# InstrumentHubs.net
KiCad netlist of a schematic drawn in EAGLE
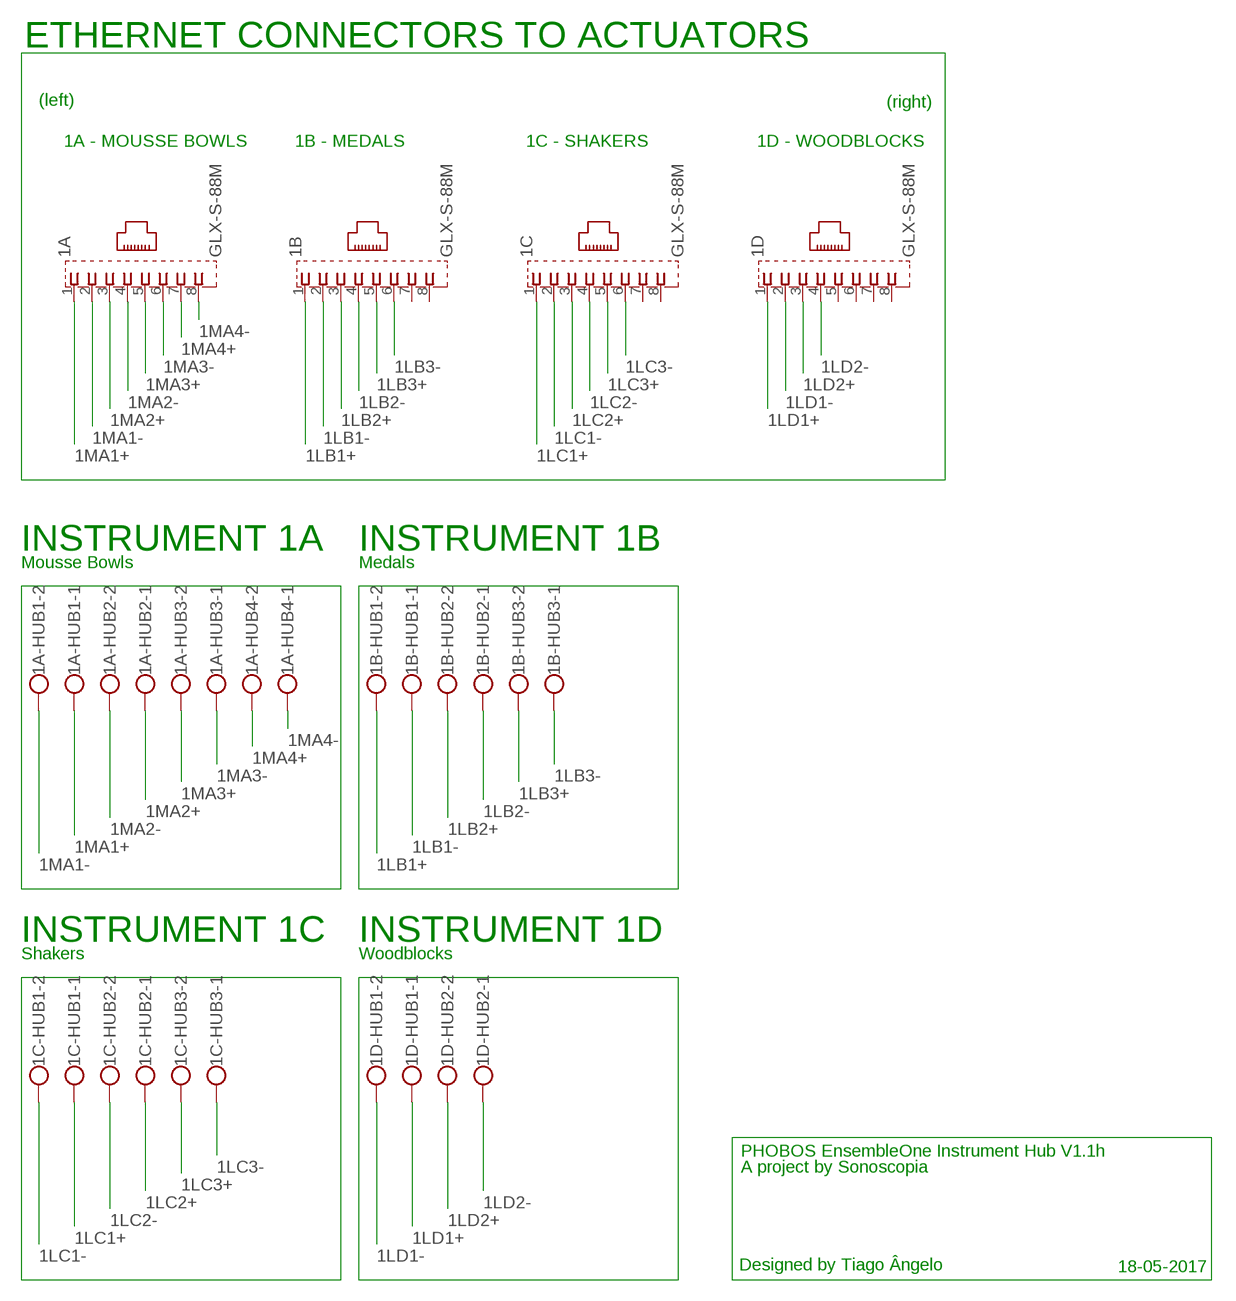
[diagram p0: schematic, sheet 1]
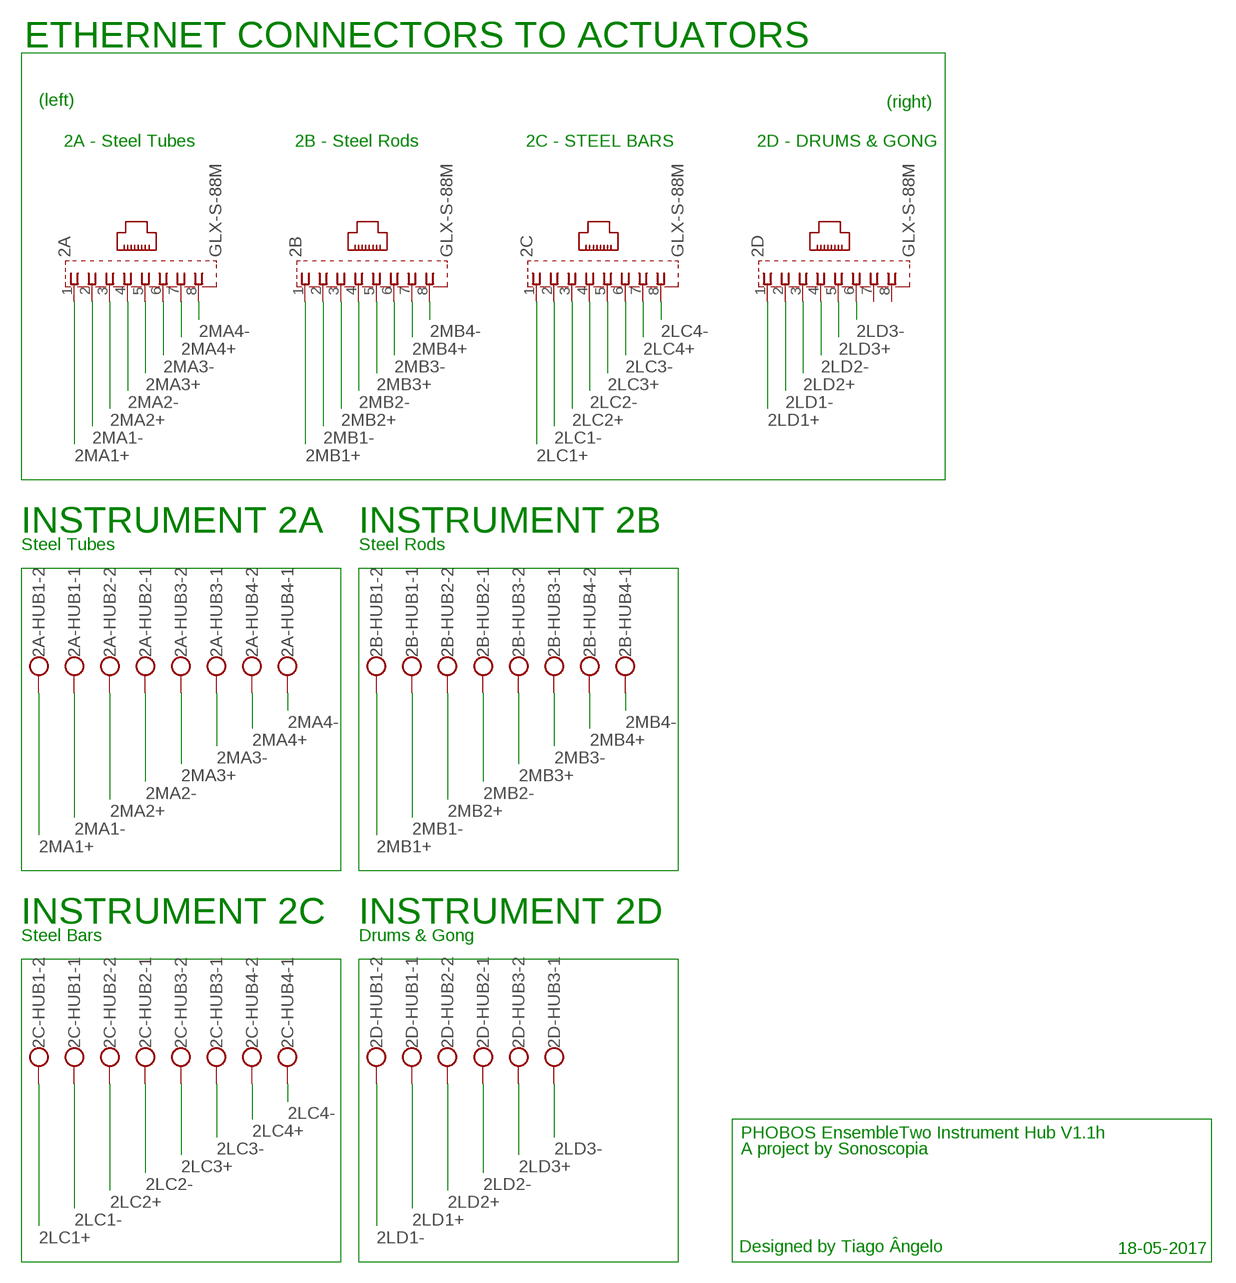
[diagram p1: schematic, sheet 2]
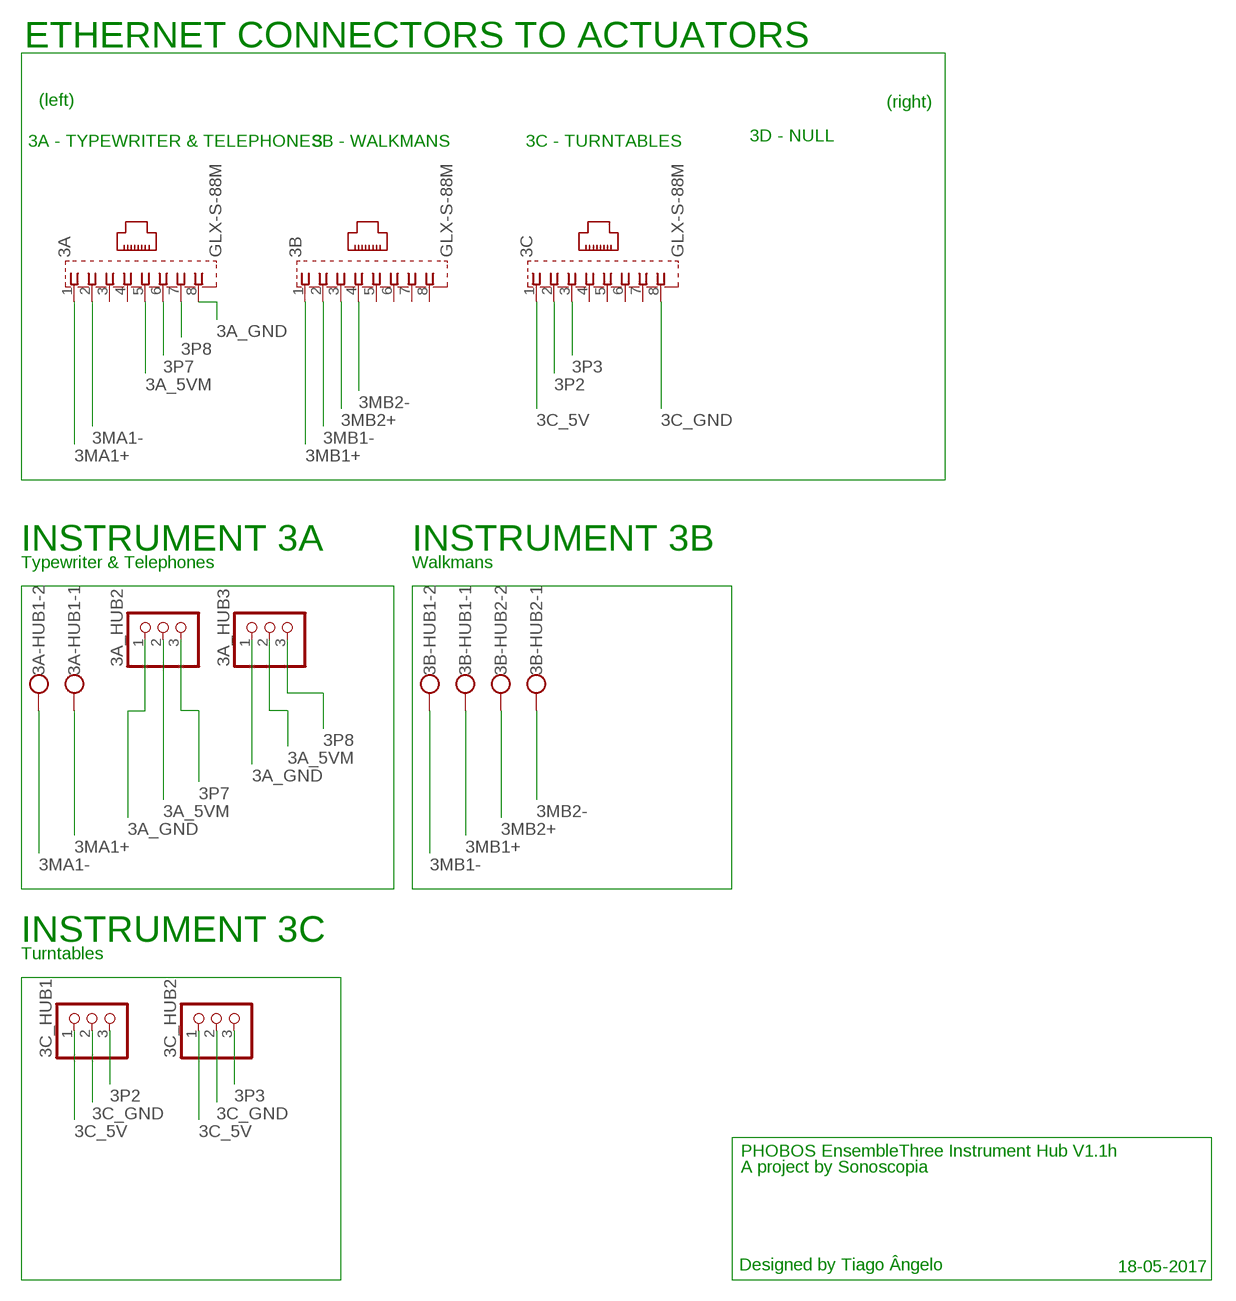
[diagram p2: schematic, sheet 3]
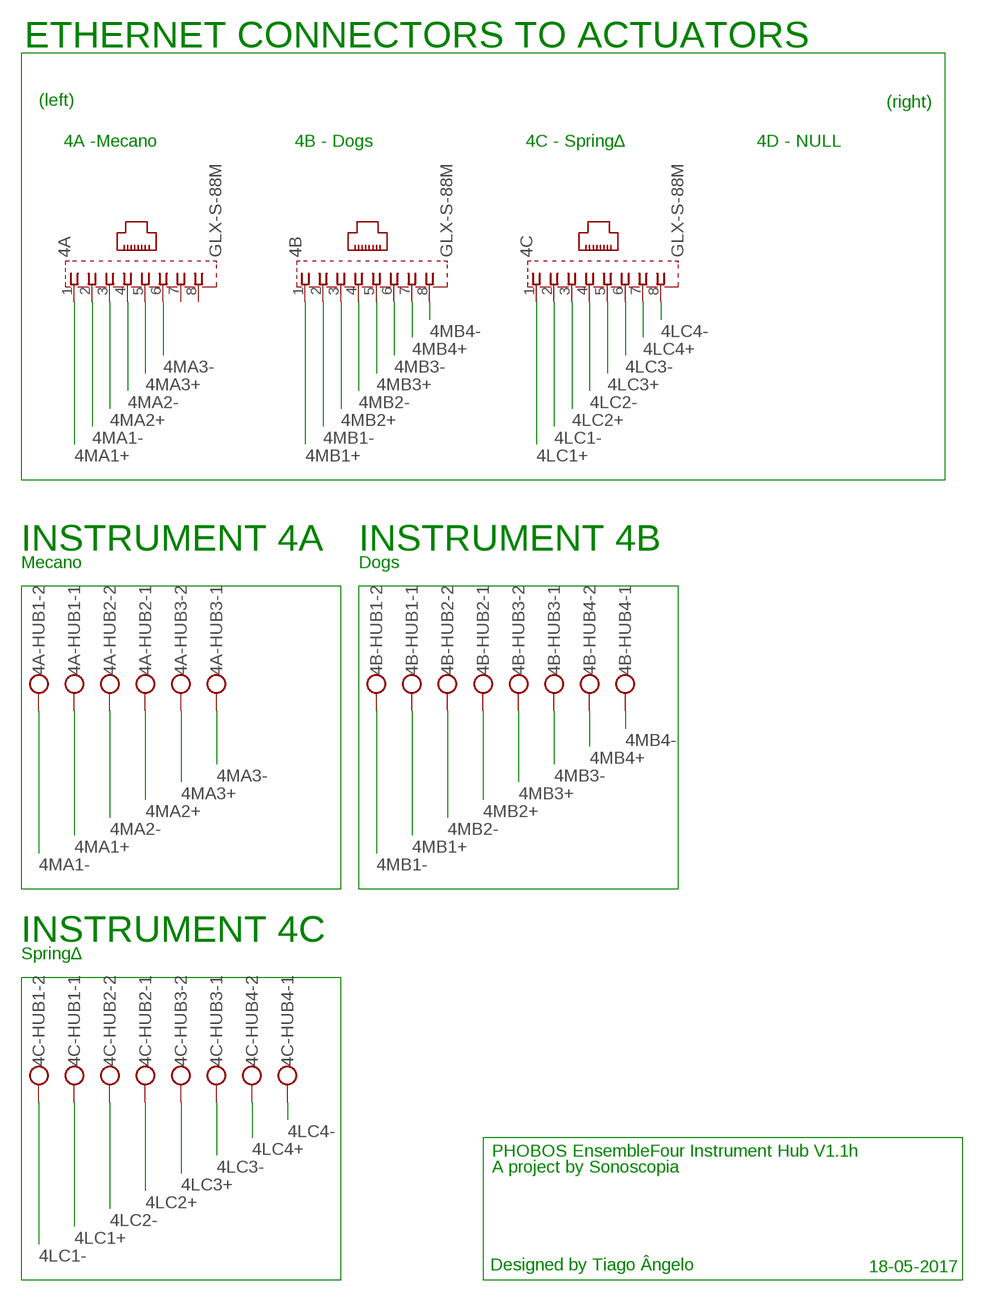
[diagram p3: schematic, sheet 4]
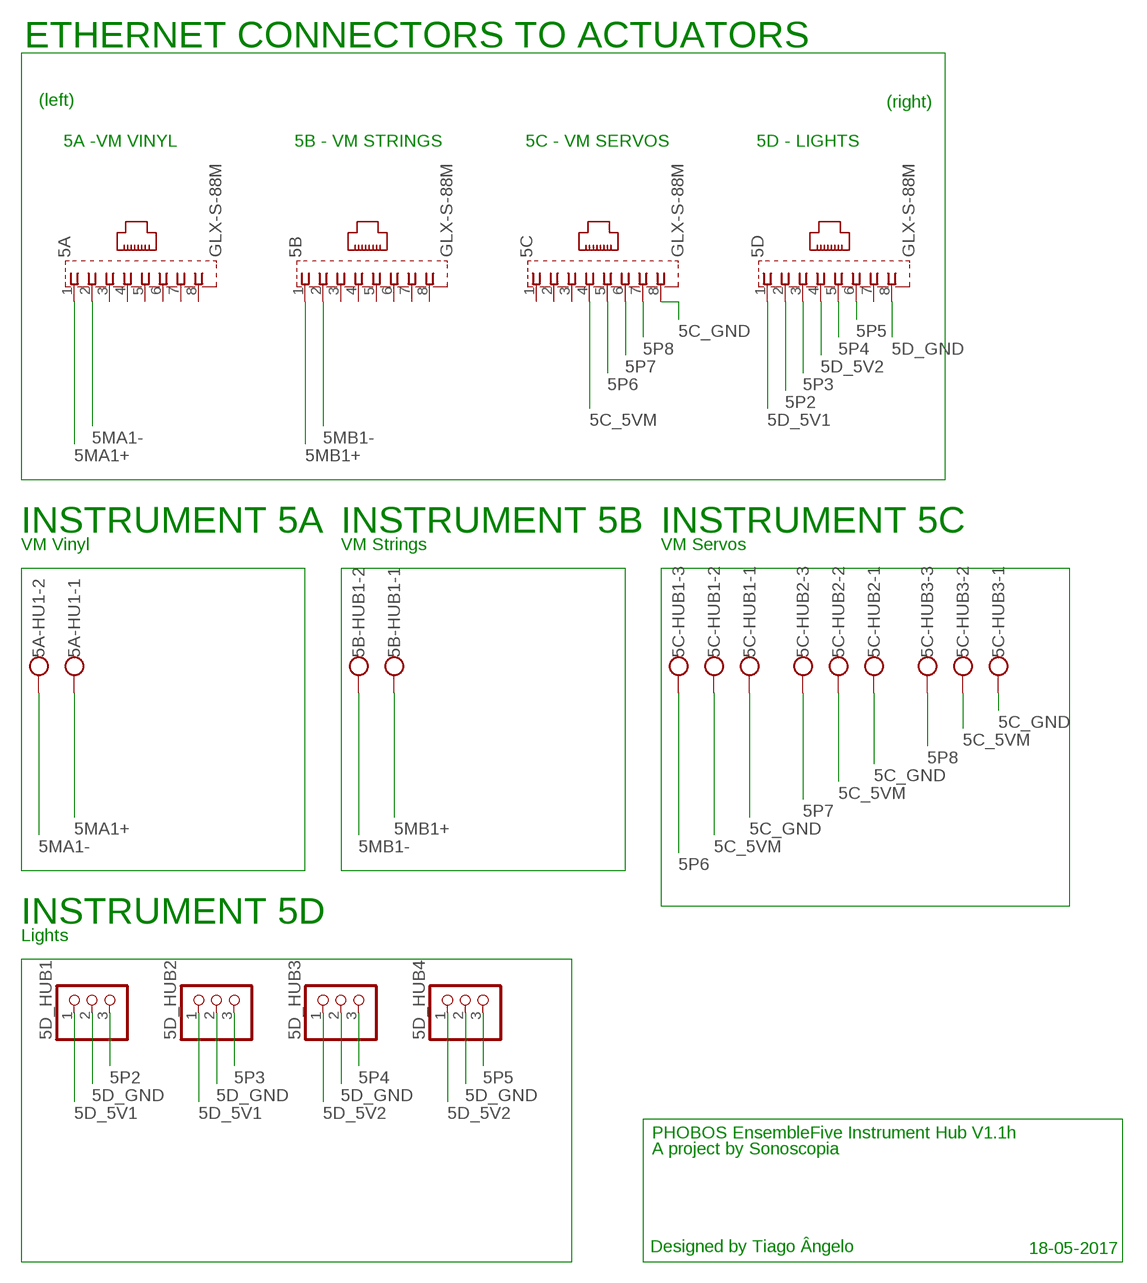
[diagram p4: schematic, sheet 5]
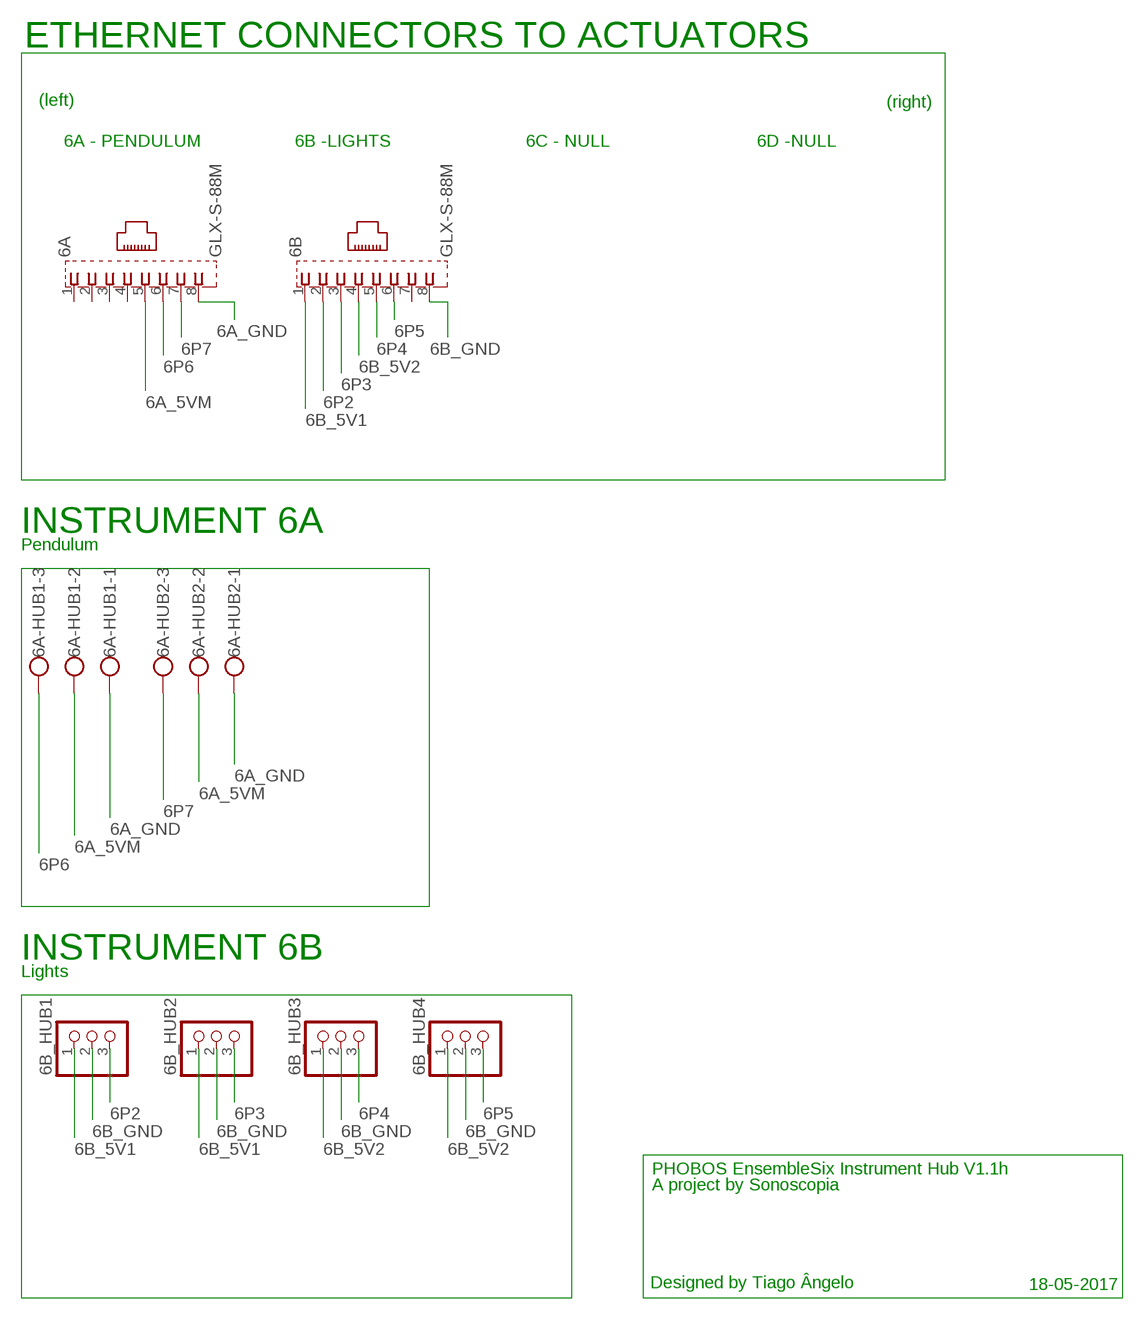
[diagram p5: schematic, sheet 6]
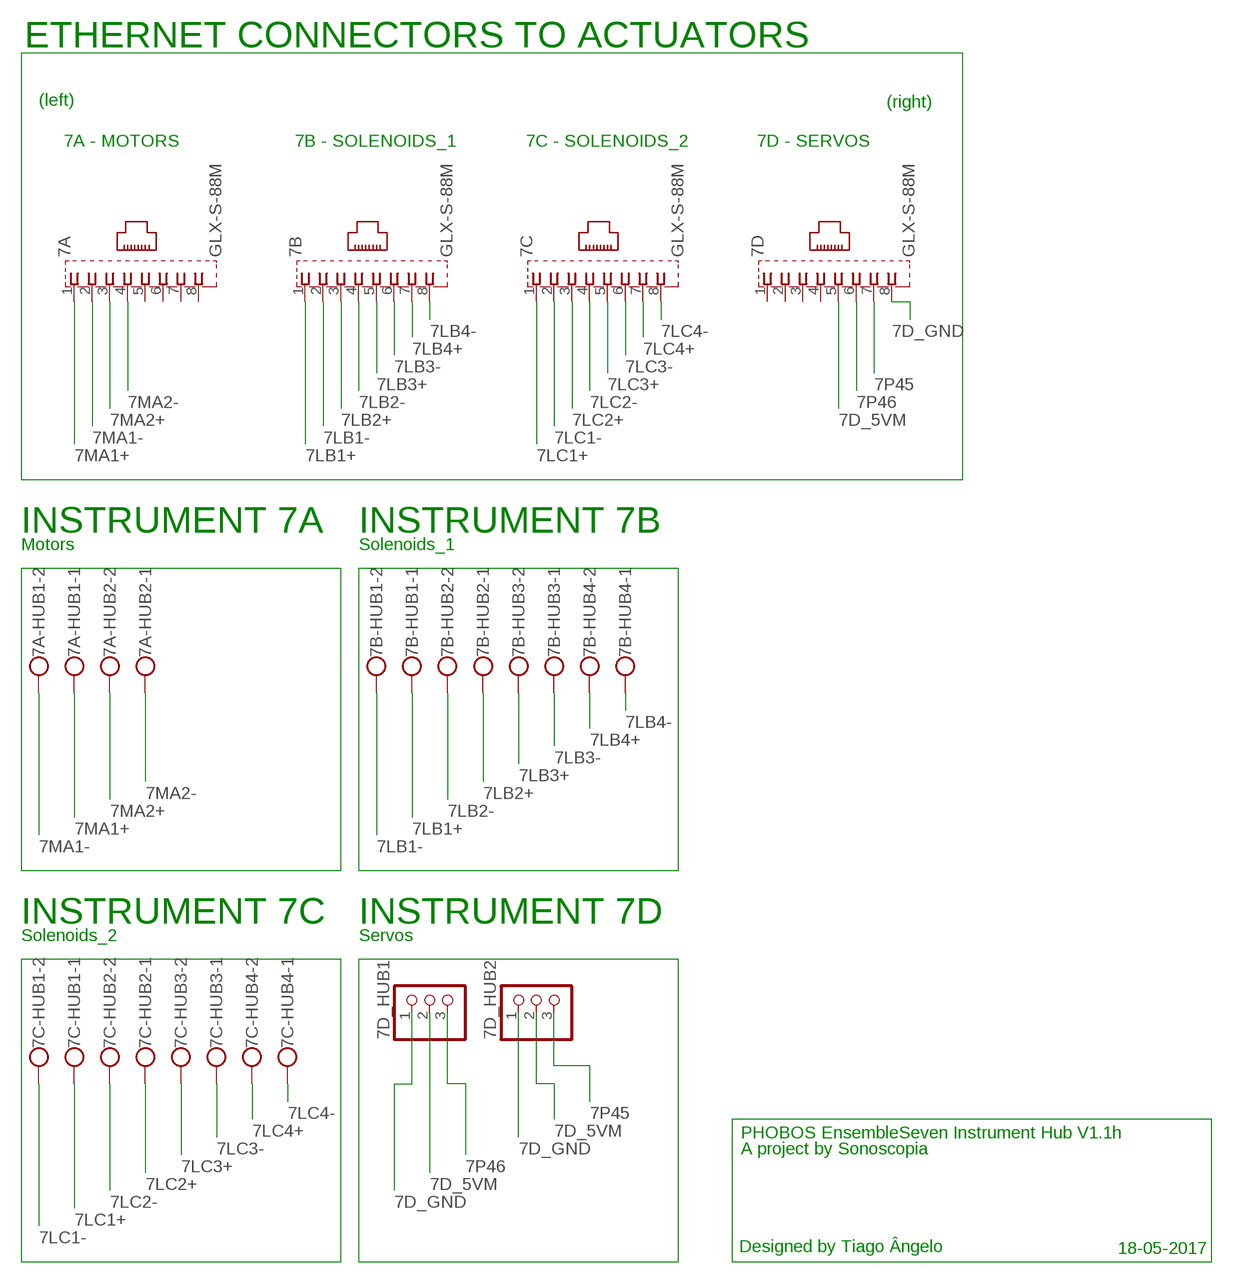
[diagram p6: schematic, sheet 7]
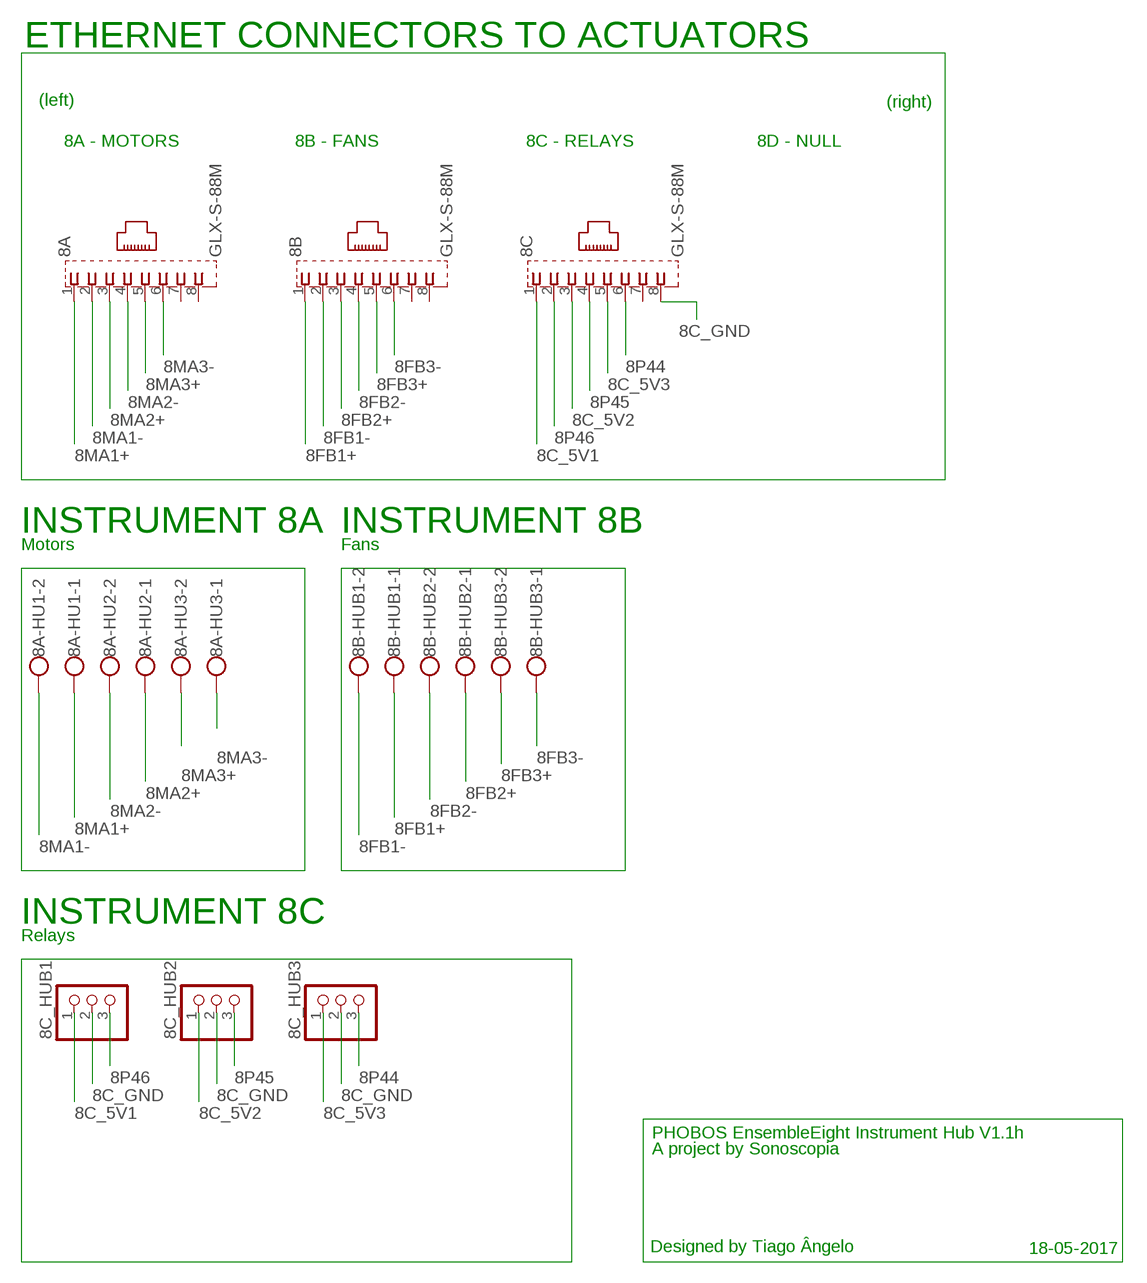
[diagram p7: schematic, sheet 8]
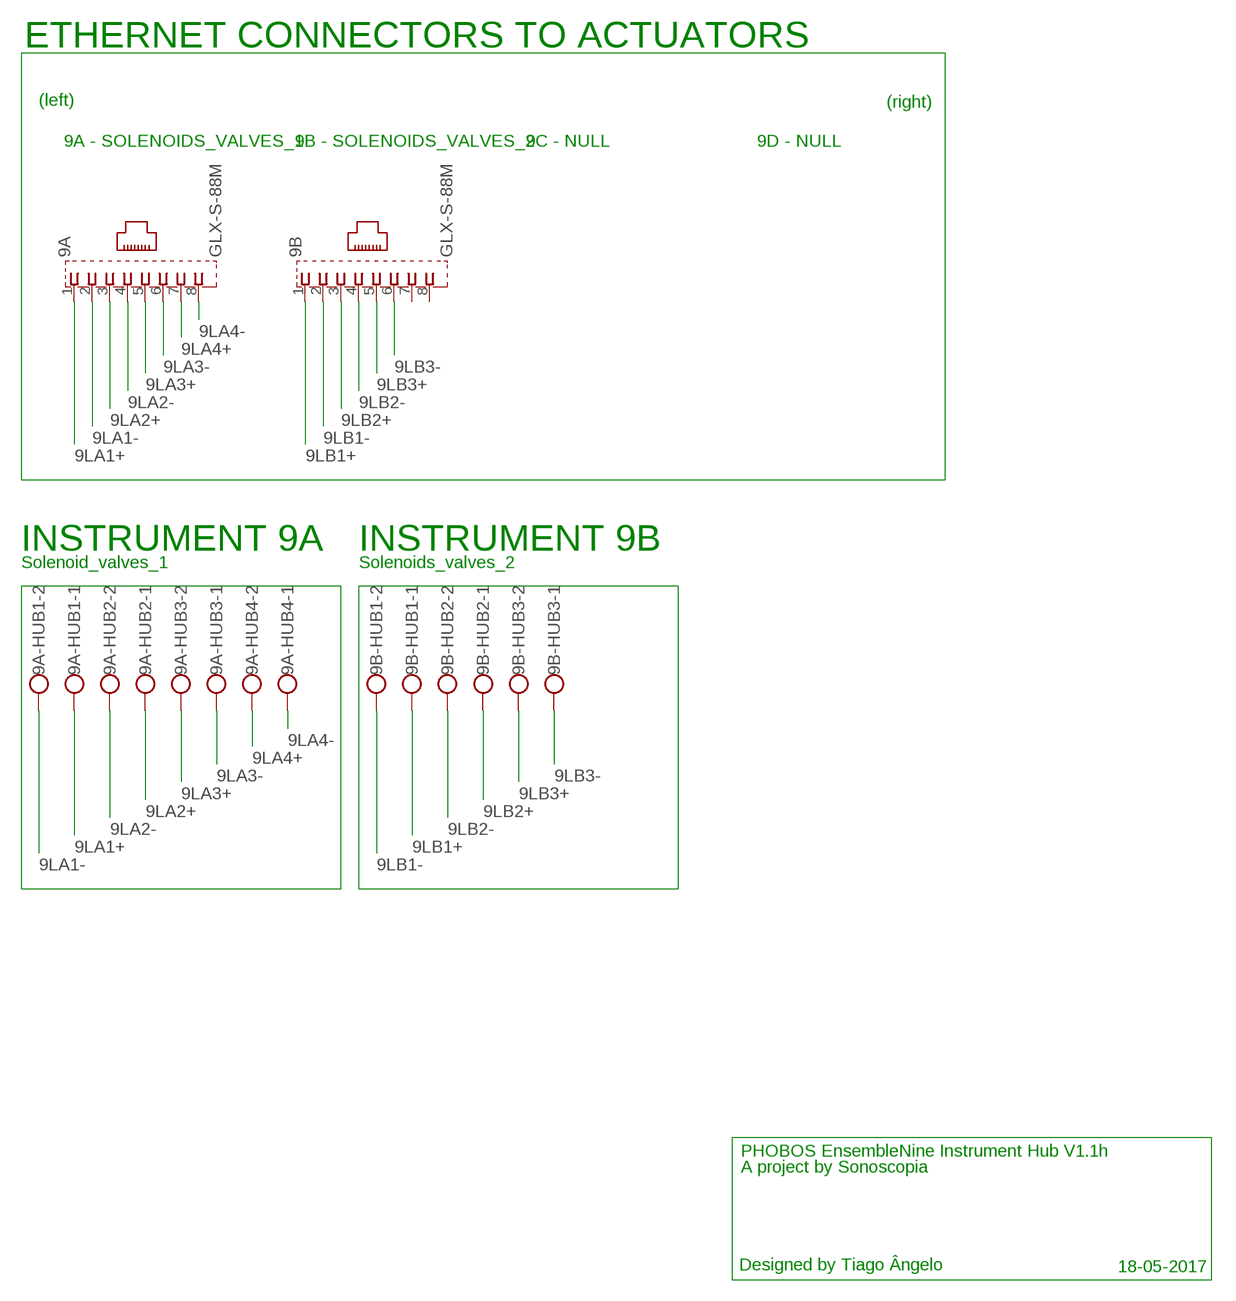
[diagram p8: schematic, sheet 9]

(export (version "E")
  (design (tool "Eeschema 10.0.6"))
  (components
    (comp (ref "7A")
      (value "GLX-S-88M")
      (footprint "eagle-import:GLX-S-88M")
      (libsource (lib "eagle-import") (part "GLX-S-88M"))
    )
    (comp (ref "7A-HUB1")
      (value "W237-102")
      (footprint "eagle-import:W237-102")
      (fields (field (name "MPN") "237-102"))
      (libsource (lib "eagle-import") (part "W237-102"))
    )
    (comp (ref "7A-HUB2")
      (value "W237-102")
      (footprint "eagle-import:W237-102")
      (fields (field (name "MPN") "237-102"))
      (libsource (lib "eagle-import") (part "W237-102"))
    )
    (comp (ref "7B")
      (value "GLX-S-88M")
      (footprint "eagle-import:GLX-S-88M")
      (libsource (lib "eagle-import") (part "GLX-S-88M"))
    )
    (comp (ref "7B-HUB1")
      (value "W237-102")
      (footprint "eagle-import:W237-102")
      (fields (field (name "MPN") "237-102"))
      (libsource (lib "eagle-import") (part "W237-102"))
    )
    (comp (ref "7B-HUB2")
      (value "W237-102")
      (footprint "eagle-import:W237-102")
      (fields (field (name "MPN") "237-102"))
      (libsource (lib "eagle-import") (part "W237-102"))
    )
    (comp (ref "7B-HUB3")
      (value "W237-102")
      (footprint "eagle-import:W237-102")
      (fields (field (name "MPN") "237-102"))
      (libsource (lib "eagle-import") (part "W237-102"))
    )
    (comp (ref "7B-HUB4")
      (value "W237-102")
      (footprint "eagle-import:W237-102")
      (fields (field (name "MPN") "237-102"))
      (libsource (lib "eagle-import") (part "W237-102"))
    )
    (comp (ref "7C")
      (value "GLX-S-88M")
      (footprint "eagle-import:GLX-S-88M")
      (libsource (lib "eagle-import") (part "GLX-S-88M"))
    )
    (comp (ref "7C-HUB1")
      (value "W237-102")
      (footprint "eagle-import:W237-102")
      (fields (field (name "MPN") "237-102"))
      (libsource (lib "eagle-import") (part "W237-102"))
    )
    (comp (ref "7C-HUB2")
      (value "W237-102")
      (footprint "eagle-import:W237-102")
      (fields (field (name "MPN") "237-102"))
      (libsource (lib "eagle-import") (part "W237-102"))
    )
    (comp (ref "7C-HUB3")
      (value "W237-102")
      (footprint "eagle-import:W237-102")
      (fields (field (name "MPN") "237-102"))
      (libsource (lib "eagle-import") (part "W237-102"))
    )
    (comp (ref "7C-HUB4")
      (value "W237-102")
      (footprint "eagle-import:W237-102")
      (fields (field (name "MPN") "237-102"))
      (libsource (lib "eagle-import") (part "W237-102"))
    )
    (comp (ref "7D")
      (value "GLX-S-88M")
      (footprint "eagle-import:GLX-S-88M")
      (libsource (lib "eagle-import") (part "GLX-S-88M"))
    )
    (comp (ref "7D_HUB1")
      (value "PINHD-1X3")
      (footprint "eagle-import:1X03")
      (libsource (lib "eagle-import") (part "PINHD-1X3"))
    )
    (comp (ref "7D_HUB2")
      (value "PINHD-1X3")
      (footprint "eagle-import:1X03")
      (libsource (lib "eagle-import") (part "PINHD-1X3"))
    )
    (comp (ref "5A")
      (value "GLX-S-88M")
      (footprint "eagle-import:GLX-S-88M")
      (libsource (lib "eagle-import") (part "GLX-S-88M"))
    )
    (comp (ref "5A-HU1")
      (value "W237-102")
      (footprint "eagle-import:W237-102")
      (fields (field (name "MPN") "237-102"))
      (libsource (lib "eagle-import") (part "W237-102"))
    )
    (comp (ref "5B")
      (value "GLX-S-88M")
      (footprint "eagle-import:GLX-S-88M")
      (libsource (lib "eagle-import") (part "GLX-S-88M"))
    )
    (comp (ref "5B-HUB1")
      (value "W237-102")
      (footprint "eagle-import:W237-102")
      (fields (field (name "MPN") "237-102"))
      (libsource (lib "eagle-import") (part "W237-102"))
    )
    (comp (ref "5C")
      (value "GLX-S-88M")
      (footprint "eagle-import:GLX-S-88M")
      (libsource (lib "eagle-import") (part "GLX-S-88M"))
    )
    (comp (ref "5C-HUB1")
      (value "W237-103")
      (footprint "eagle-import:W237-103")
      (fields (field (name "MPN") "237-103"))
      (libsource (lib "eagle-import") (part "W237-103"))
    )
    (comp (ref "5C-HUB2")
      (value "W237-103")
      (footprint "eagle-import:W237-103")
      (fields (field (name "MPN") "237-103"))
      (libsource (lib "eagle-import") (part "W237-103"))
    )
    (comp (ref "5C-HUB3")
      (value "W237-103")
      (footprint "eagle-import:W237-103")
      (fields (field (name "MPN") "237-103"))
      (libsource (lib "eagle-import") (part "W237-103"))
    )
    (comp (ref "5D")
      (value "GLX-S-88M")
      (footprint "eagle-import:GLX-S-88M")
      (libsource (lib "eagle-import") (part "GLX-S-88M"))
    )
    (comp (ref "5D_HUB1")
      (value "PINHD-1X3")
      (footprint "eagle-import:1X03")
      (libsource (lib "eagle-import") (part "PINHD-1X3"))
    )
    (comp (ref "5D_HUB2")
      (value "PINHD-1X3")
      (footprint "eagle-import:1X03")
      (libsource (lib "eagle-import") (part "PINHD-1X3"))
    )
    (comp (ref "5D_HUB3")
      (value "PINHD-1X3")
      (footprint "eagle-import:1X03")
      (libsource (lib "eagle-import") (part "PINHD-1X3"))
    )
    (comp (ref "5D_HUB4")
      (value "PINHD-1X3")
      (footprint "eagle-import:1X03")
      (libsource (lib "eagle-import") (part "PINHD-1X3"))
    )
    (comp (ref "8A")
      (value "GLX-S-88M")
      (footprint "eagle-import:GLX-S-88M")
      (libsource (lib "eagle-import") (part "GLX-S-88M"))
    )
    (comp (ref "8A-HU1")
      (value "W237-102")
      (footprint "eagle-import:W237-102")
      (fields (field (name "MPN") "237-102"))
      (libsource (lib "eagle-import") (part "W237-102"))
    )
    (comp (ref "8A-HU2")
      (value "W237-102")
      (footprint "eagle-import:W237-102")
      (fields (field (name "MPN") "237-102"))
      (libsource (lib "eagle-import") (part "W237-102"))
    )
    (comp (ref "8A-HU3")
      (value "W237-102")
      (footprint "eagle-import:W237-102")
      (fields (field (name "MPN") "237-102"))
      (libsource (lib "eagle-import") (part "W237-102"))
    )
    (comp (ref "8B")
      (value "GLX-S-88M")
      (footprint "eagle-import:GLX-S-88M")
      (libsource (lib "eagle-import") (part "GLX-S-88M"))
    )
    (comp (ref "8B-HUB1")
      (value "W237-102")
      (footprint "eagle-import:W237-102")
      (fields (field (name "MPN") "237-102"))
      (libsource (lib "eagle-import") (part "W237-102"))
    )
    (comp (ref "8B-HUB2")
      (value "W237-102")
      (footprint "eagle-import:W237-102")
      (fields (field (name "MPN") "237-102"))
      (libsource (lib "eagle-import") (part "W237-102"))
    )
    (comp (ref "8B-HUB3")
      (value "W237-102")
      (footprint "eagle-import:W237-102")
      (fields (field (name "MPN") "237-102"))
      (libsource (lib "eagle-import") (part "W237-102"))
    )
    (comp (ref "8C")
      (value "GLX-S-88M")
      (footprint "eagle-import:GLX-S-88M")
      (libsource (lib "eagle-import") (part "GLX-S-88M"))
    )
    (comp (ref "8C_HUB1")
      (value "PINHD-1X3")
      (footprint "eagle-import:1X03")
      (libsource (lib "eagle-import") (part "PINHD-1X3"))
    )
    (comp (ref "8C_HUB2")
      (value "PINHD-1X3")
      (footprint "eagle-import:1X03")
      (libsource (lib "eagle-import") (part "PINHD-1X3"))
    )
    (comp (ref "8C_HUB3")
      (value "PINHD-1X3")
      (footprint "eagle-import:1X03")
      (libsource (lib "eagle-import") (part "PINHD-1X3"))
    )
    (comp (ref "4A")
      (value "GLX-S-88M")
      (footprint "eagle-import:GLX-S-88M")
      (libsource (lib "eagle-import") (part "GLX-S-88M"))
    )
    (comp (ref "4A-HUB1")
      (value "W237-102")
      (footprint "eagle-import:W237-102")
      (fields (field (name "MPN") "237-102"))
      (libsource (lib "eagle-import") (part "W237-102"))
    )
    (comp (ref "4A-HUB2")
      (value "W237-102")
      (footprint "eagle-import:W237-102")
      (fields (field (name "MPN") "237-102"))
      (libsource (lib "eagle-import") (part "W237-102"))
    )
    (comp (ref "4A-HUB3")
      (value "W237-102")
      (footprint "eagle-import:W237-102")
      (fields (field (name "MPN") "237-102"))
      (libsource (lib "eagle-import") (part "W237-102"))
    )
    (comp (ref "4B")
      (value "GLX-S-88M")
      (footprint "eagle-import:GLX-S-88M")
      (libsource (lib "eagle-import") (part "GLX-S-88M"))
    )
    (comp (ref "4B-HUB1")
      (value "W237-102")
      (footprint "eagle-import:W237-102")
      (fields (field (name "MPN") "237-102"))
      (libsource (lib "eagle-import") (part "W237-102"))
    )
    (comp (ref "4B-HUB2")
      (value "W237-102")
      (footprint "eagle-import:W237-102")
      (fields (field (name "MPN") "237-102"))
      (libsource (lib "eagle-import") (part "W237-102"))
    )
    (comp (ref "4B-HUB3")
      (value "W237-102")
      (footprint "eagle-import:W237-102")
      (fields (field (name "MPN") "237-102"))
      (libsource (lib "eagle-import") (part "W237-102"))
    )
    (comp (ref "4B-HUB4")
      (value "W237-102")
      (footprint "eagle-import:W237-102")
      (fields (field (name "MPN") "237-102"))
      (libsource (lib "eagle-import") (part "W237-102"))
    )
    (comp (ref "4C")
      (value "GLX-S-88M")
      (footprint "eagle-import:GLX-S-88M")
      (libsource (lib "eagle-import") (part "GLX-S-88M"))
    )
    (comp (ref "4C-HUB1")
      (value "W237-102")
      (footprint "eagle-import:W237-102")
      (fields (field (name "MPN") "237-102"))
      (libsource (lib "eagle-import") (part "W237-102"))
    )
    (comp (ref "4C-HUB2")
      (value "W237-102")
      (footprint "eagle-import:W237-102")
      (fields (field (name "MPN") "237-102"))
      (libsource (lib "eagle-import") (part "W237-102"))
    )
    (comp (ref "4C-HUB3")
      (value "W237-102")
      (footprint "eagle-import:W237-102")
      (fields (field (name "MPN") "237-102"))
      (libsource (lib "eagle-import") (part "W237-102"))
    )
    (comp (ref "4C-HUB4")
      (value "W237-102")
      (footprint "eagle-import:W237-102")
      (fields (field (name "MPN") "237-102"))
      (libsource (lib "eagle-import") (part "W237-102"))
    )
    (comp (ref "1A")
      (value "GLX-S-88M")
      (footprint "eagle-import:GLX-S-88M")
      (libsource (lib "eagle-import") (part "GLX-S-88M"))
    )
    (comp (ref "1A-HUB1")
      (value "W237-102")
      (footprint "eagle-import:W237-102")
      (fields (field (name "MPN") "237-102"))
      (libsource (lib "eagle-import") (part "W237-102"))
    )
    (comp (ref "1A-HUB2")
      (value "W237-102")
      (footprint "eagle-import:W237-102")
      (fields (field (name "MPN") "237-102"))
      (libsource (lib "eagle-import") (part "W237-102"))
    )
    (comp (ref "1A-HUB3")
      (value "W237-102")
      (footprint "eagle-import:W237-102")
      (fields (field (name "MPN") "237-102"))
      (libsource (lib "eagle-import") (part "W237-102"))
    )
    (comp (ref "1A-HUB4")
      (value "W237-102")
      (footprint "eagle-import:W237-102")
      (fields (field (name "MPN") "237-102"))
      (libsource (lib "eagle-import") (part "W237-102"))
    )
    (comp (ref "1B")
      (value "GLX-S-88M")
      (footprint "eagle-import:GLX-S-88M")
      (libsource (lib "eagle-import") (part "GLX-S-88M"))
    )
    (comp (ref "1B-HUB1")
      (value "W237-102")
      (footprint "eagle-import:W237-102")
      (fields (field (name "MPN") "237-102"))
      (libsource (lib "eagle-import") (part "W237-102"))
    )
    (comp (ref "1B-HUB2")
      (value "W237-102")
      (footprint "eagle-import:W237-102")
      (fields (field (name "MPN") "237-102"))
      (libsource (lib "eagle-import") (part "W237-102"))
    )
    (comp (ref "1B-HUB3")
      (value "W237-102")
      (footprint "eagle-import:W237-102")
      (fields (field (name "MPN") "237-102"))
      (libsource (lib "eagle-import") (part "W237-102"))
    )
    (comp (ref "1C")
      (value "GLX-S-88M")
      (footprint "eagle-import:GLX-S-88M")
      (libsource (lib "eagle-import") (part "GLX-S-88M"))
    )
    (comp (ref "1C-HUB1")
      (value "W237-102")
      (footprint "eagle-import:W237-102")
      (fields (field (name "MPN") "237-102"))
      (libsource (lib "eagle-import") (part "W237-102"))
    )
    (comp (ref "1C-HUB2")
      (value "W237-102")
      (footprint "eagle-import:W237-102")
      (fields (field (name "MPN") "237-102"))
      (libsource (lib "eagle-import") (part "W237-102"))
    )
    (comp (ref "1C-HUB3")
      (value "W237-102")
      (footprint "eagle-import:W237-102")
      (fields (field (name "MPN") "237-102"))
      (libsource (lib "eagle-import") (part "W237-102"))
    )
    (comp (ref "1D")
      (value "GLX-S-88M")
      (footprint "eagle-import:GLX-S-88M")
      (libsource (lib "eagle-import") (part "GLX-S-88M"))
    )
    (comp (ref "1D-HUB1")
      (value "W237-102")
      (footprint "eagle-import:W237-102")
      (fields (field (name "MPN") "237-102"))
      (libsource (lib "eagle-import") (part "W237-102"))
    )
    (comp (ref "1D-HUB2")
      (value "W237-102")
      (footprint "eagle-import:W237-102")
      (fields (field (name "MPN") "237-102"))
      (libsource (lib "eagle-import") (part "W237-102"))
    )
    (comp (ref "2A")
      (value "GLX-S-88M")
      (footprint "eagle-import:GLX-S-88M")
      (libsource (lib "eagle-import") (part "GLX-S-88M"))
    )
    (comp (ref "2A-HUB1")
      (value "W237-102")
      (footprint "eagle-import:W237-102")
      (fields (field (name "MPN") "237-102"))
      (libsource (lib "eagle-import") (part "W237-102"))
    )
    (comp (ref "2A-HUB2")
      (value "W237-102")
      (footprint "eagle-import:W237-102")
      (fields (field (name "MPN") "237-102"))
      (libsource (lib "eagle-import") (part "W237-102"))
    )
    (comp (ref "2A-HUB3")
      (value "W237-102")
      (footprint "eagle-import:W237-102")
      (fields (field (name "MPN") "237-102"))
      (libsource (lib "eagle-import") (part "W237-102"))
    )
    (comp (ref "2A-HUB4")
      (value "W237-102")
      (footprint "eagle-import:W237-102")
      (fields (field (name "MPN") "237-102"))
      (libsource (lib "eagle-import") (part "W237-102"))
    )
    (comp (ref "2B")
      (value "GLX-S-88M")
      (footprint "eagle-import:GLX-S-88M")
      (libsource (lib "eagle-import") (part "GLX-S-88M"))
    )
    (comp (ref "2B-HUB1")
      (value "W237-102")
      (footprint "eagle-import:W237-102")
      (fields (field (name "MPN") "237-102"))
      (libsource (lib "eagle-import") (part "W237-102"))
    )
    (comp (ref "2B-HUB2")
      (value "W237-102")
      (footprint "eagle-import:W237-102")
      (fields (field (name "MPN") "237-102"))
      (libsource (lib "eagle-import") (part "W237-102"))
    )
    (comp (ref "2B-HUB3")
      (value "W237-102")
      (footprint "eagle-import:W237-102")
      (fields (field (name "MPN") "237-102"))
      (libsource (lib "eagle-import") (part "W237-102"))
    )
    (comp (ref "2B-HUB4")
      (value "W237-102")
      (footprint "eagle-import:W237-102")
      (fields (field (name "MPN") "237-102"))
      (libsource (lib "eagle-import") (part "W237-102"))
    )
    (comp (ref "2C")
      (value "GLX-S-88M")
      (footprint "eagle-import:GLX-S-88M")
      (libsource (lib "eagle-import") (part "GLX-S-88M"))
    )
    (comp (ref "2C-HUB1")
      (value "W237-102")
      (footprint "eagle-import:W237-102")
      (fields (field (name "MPN") "237-102"))
      (libsource (lib "eagle-import") (part "W237-102"))
    )
    (comp (ref "2C-HUB2")
      (value "W237-102")
      (footprint "eagle-import:W237-102")
      (fields (field (name "MPN") "237-102"))
      (libsource (lib "eagle-import") (part "W237-102"))
    )
    (comp (ref "2C-HUB3")
      (value "W237-102")
      (footprint "eagle-import:W237-102")
      (fields (field (name "MPN") "237-102"))
      (libsource (lib "eagle-import") (part "W237-102"))
    )
    (comp (ref "2C-HUB4")
      (value "W237-102")
      (footprint "eagle-import:W237-102")
      (fields (field (name "MPN") "237-102"))
      (libsource (lib "eagle-import") (part "W237-102"))
    )
    (comp (ref "2D")
      (value "GLX-S-88M")
      (footprint "eagle-import:GLX-S-88M")
      (libsource (lib "eagle-import") (part "GLX-S-88M"))
    )
    (comp (ref "2D-HUB1")
      (value "W237-102")
      (footprint "eagle-import:W237-102")
      (fields (field (name "MPN") "237-102"))
      (libsource (lib "eagle-import") (part "W237-102"))
    )
    (comp (ref "2D-HUB2")
      (value "W237-102")
      (footprint "eagle-import:W237-102")
      (fields (field (name "MPN") "237-102"))
      (libsource (lib "eagle-import") (part "W237-102"))
    )
    (comp (ref "2D-HUB3")
      (value "W237-102")
      (footprint "eagle-import:W237-102")
      (fields (field (name "MPN") "237-102"))
      (libsource (lib "eagle-import") (part "W237-102"))
    )
    (comp (ref "6A")
      (value "GLX-S-88M")
      (footprint "eagle-import:GLX-S-88M")
      (libsource (lib "eagle-import") (part "GLX-S-88M"))
    )
    (comp (ref "6A-HUB1")
      (value "W237-103")
      (footprint "eagle-import:W237-103")
      (fields (field (name "MPN") "237-103"))
      (libsource (lib "eagle-import") (part "W237-103"))
    )
    (comp (ref "6A-HUB2")
      (value "W237-103")
      (footprint "eagle-import:W237-103")
      (fields (field (name "MPN") "237-103"))
      (libsource (lib "eagle-import") (part "W237-103"))
    )
    (comp (ref "6B")
      (value "GLX-S-88M")
      (footprint "eagle-import:GLX-S-88M")
      (libsource (lib "eagle-import") (part "GLX-S-88M"))
    )
    (comp (ref "6B_HUB1")
      (value "PINHD-1X3")
      (footprint "eagle-import:1X03")
      (libsource (lib "eagle-import") (part "PINHD-1X3"))
    )
    (comp (ref "6B_HUB2")
      (value "PINHD-1X3")
      (footprint "eagle-import:1X03")
      (libsource (lib "eagle-import") (part "PINHD-1X3"))
    )
    (comp (ref "6B_HUB3")
      (value "PINHD-1X3")
      (footprint "eagle-import:1X03")
      (libsource (lib "eagle-import") (part "PINHD-1X3"))
    )
    (comp (ref "6B_HUB4")
      (value "PINHD-1X3")
      (footprint "eagle-import:1X03")
      (libsource (lib "eagle-import") (part "PINHD-1X3"))
    )
    (comp (ref "3A")
      (value "GLX-S-88M")
      (footprint "eagle-import:GLX-S-88M")
      (libsource (lib "eagle-import") (part "GLX-S-88M"))
    )
    (comp (ref "3A-HUB1")
      (value "W237-102")
      (footprint "eagle-import:W237-102")
      (fields (field (name "MPN") "237-102"))
      (libsource (lib "eagle-import") (part "W237-102"))
    )
    (comp (ref "3A_HUB2")
      (value "PINHD-1X3")
      (footprint "eagle-import:1X03")
      (libsource (lib "eagle-import") (part "PINHD-1X3"))
    )
    (comp (ref "3A_HUB3")
      (value "PINHD-1X3")
      (footprint "eagle-import:1X03")
      (libsource (lib "eagle-import") (part "PINHD-1X3"))
    )
    (comp (ref "3B")
      (value "GLX-S-88M")
      (footprint "eagle-import:GLX-S-88M")
      (libsource (lib "eagle-import") (part "GLX-S-88M"))
    )
    (comp (ref "3B-HUB1")
      (value "W237-102")
      (footprint "eagle-import:W237-102")
      (fields (field (name "MPN") "237-102"))
      (libsource (lib "eagle-import") (part "W237-102"))
    )
    (comp (ref "3B-HUB2")
      (value "W237-102")
      (footprint "eagle-import:W237-102")
      (fields (field (name "MPN") "237-102"))
      (libsource (lib "eagle-import") (part "W237-102"))
    )
    (comp (ref "3C")
      (value "GLX-S-88M")
      (footprint "eagle-import:GLX-S-88M")
      (libsource (lib "eagle-import") (part "GLX-S-88M"))
    )
    (comp (ref "3C_HUB1")
      (value "PINHD-1X3")
      (footprint "eagle-import:1X03")
      (libsource (lib "eagle-import") (part "PINHD-1X3"))
    )
    (comp (ref "3C_HUB2")
      (value "PINHD-1X3")
      (footprint "eagle-import:1X03")
      (libsource (lib "eagle-import") (part "PINHD-1X3"))
    )
    (comp (ref "9A")
      (value "GLX-S-88M")
      (footprint "eagle-import:GLX-S-88M")
      (libsource (lib "eagle-import") (part "GLX-S-88M"))
    )
    (comp (ref "9A-HUB1")
      (value "W237-102")
      (footprint "eagle-import:W237-102")
      (fields (field (name "MPN") "237-102"))
      (libsource (lib "eagle-import") (part "W237-102"))
    )
    (comp (ref "9A-HUB2")
      (value "W237-102")
      (footprint "eagle-import:W237-102")
      (fields (field (name "MPN") "237-102"))
      (libsource (lib "eagle-import") (part "W237-102"))
    )
    (comp (ref "9A-HUB3")
      (value "W237-102")
      (footprint "eagle-import:W237-102")
      (fields (field (name "MPN") "237-102"))
      (libsource (lib "eagle-import") (part "W237-102"))
    )
    (comp (ref "9A-HUB4")
      (value "W237-102")
      (footprint "eagle-import:W237-102")
      (fields (field (name "MPN") "237-102"))
      (libsource (lib "eagle-import") (part "W237-102"))
    )
    (comp (ref "9B")
      (value "GLX-S-88M")
      (footprint "eagle-import:GLX-S-88M")
      (libsource (lib "eagle-import") (part "GLX-S-88M"))
    )
    (comp (ref "9B-HUB1")
      (value "W237-102")
      (footprint "eagle-import:W237-102")
      (fields (field (name "MPN") "237-102"))
      (libsource (lib "eagle-import") (part "W237-102"))
    )
    (comp (ref "9B-HUB2")
      (value "W237-102")
      (footprint "eagle-import:W237-102")
      (fields (field (name "MPN") "237-102"))
      (libsource (lib "eagle-import") (part "W237-102"))
    )
    (comp (ref "9B-HUB3")
      (value "W237-102")
      (footprint "eagle-import:W237-102")
      (fields (field (name "MPN") "237-102"))
      (libsource (lib "eagle-import") (part "W237-102"))
    )
  )
  (nets
    (net (code "1") (name "1LB1+") (class "Default")
      (node (ref "1B") (pin "1") (pinfunction "1_1") (pintype "passive"))
      (node (ref "1B-HUB1") (pin "2") (pinfunction "KL_2") (pintype "passive"))
    )
    (net (code "2") (name "1LB1-") (class "Default")
      (node (ref "1B") (pin "2") (pinfunction "2_2") (pintype "passive"))
      (node (ref "1B-HUB1") (pin "1") (pinfunction "KL_1") (pintype "passive"))
    )
    (net (code "3") (name "1LB2+") (class "Default")
      (node (ref "1B") (pin "3") (pinfunction "3_3") (pintype "passive"))
      (node (ref "1B-HUB2") (pin "2") (pinfunction "KL_2") (pintype "passive"))
    )
    (net (code "4") (name "1LB2-") (class "Default")
      (node (ref "1B") (pin "4") (pinfunction "4_4") (pintype "passive"))
      (node (ref "1B-HUB2") (pin "1") (pinfunction "KL_1") (pintype "passive"))
    )
    (net (code "5") (name "1LB3+") (class "Default")
      (node (ref "1B") (pin "5") (pinfunction "5_5") (pintype "passive"))
      (node (ref "1B-HUB3") (pin "2") (pinfunction "KL_2") (pintype "passive"))
    )
    (net (code "6") (name "1LB3-") (class "Default")
      (node (ref "1B") (pin "6") (pinfunction "6_6") (pintype "passive"))
      (node (ref "1B-HUB3") (pin "1") (pinfunction "KL_1") (pintype "passive"))
    )
    (net (code "7") (name "1LC1+") (class "Default")
      (node (ref "1C") (pin "1") (pinfunction "1_1") (pintype "passive"))
      (node (ref "1C-HUB1") (pin "1") (pinfunction "KL_1") (pintype "passive"))
    )
    (net (code "8") (name "1LC1-") (class "Default")
      (node (ref "1C") (pin "2") (pinfunction "2_2") (pintype "passive"))
      (node (ref "1C-HUB1") (pin "2") (pinfunction "KL_2") (pintype "passive"))
    )
    (net (code "9") (name "1LC2+") (class "Default")
      (node (ref "1C") (pin "3") (pinfunction "3_3") (pintype "passive"))
      (node (ref "1C-HUB2") (pin "1") (pinfunction "KL_1") (pintype "passive"))
    )
    (net (code "10") (name "1LC2-") (class "Default")
      (node (ref "1C") (pin "4") (pinfunction "4_4") (pintype "passive"))
      (node (ref "1C-HUB2") (pin "2") (pinfunction "KL_2") (pintype "passive"))
    )
    (net (code "11") (name "1LC3+") (class "Default")
      (node (ref "1C") (pin "5") (pinfunction "5_5") (pintype "passive"))
      (node (ref "1C-HUB3") (pin "2") (pinfunction "KL_2") (pintype "passive"))
    )
    (net (code "12") (name "1LC3-") (class "Default")
      (node (ref "1C") (pin "6") (pinfunction "6_6") (pintype "passive"))
      (node (ref "1C-HUB3") (pin "1") (pinfunction "KL_1") (pintype "passive"))
    )
    (net (code "13") (name "1LD1+") (class "Default")
      (node (ref "1D") (pin "1") (pinfunction "1_1") (pintype "passive"))
      (node (ref "1D-HUB1") (pin "1") (pinfunction "KL_1") (pintype "passive"))
    )
    (net (code "14") (name "1LD1-") (class "Default")
      (node (ref "1D") (pin "2") (pinfunction "2_2") (pintype "passive"))
      (node (ref "1D-HUB1") (pin "2") (pinfunction "KL_2") (pintype "passive"))
    )
    (net (code "15") (name "1LD2+") (class "Default")
      (node (ref "1D") (pin "3") (pinfunction "3_3") (pintype "passive"))
      (node (ref "1D-HUB2") (pin "2") (pinfunction "KL_2") (pintype "passive"))
    )
    (net (code "16") (name "1LD2-") (class "Default")
      (node (ref "1D") (pin "4") (pinfunction "4_4") (pintype "passive"))
      (node (ref "1D-HUB2") (pin "1") (pinfunction "KL_1") (pintype "passive"))
    )
    (net (code "17") (name "1MA1+") (class "Default")
      (node (ref "1A") (pin "1") (pinfunction "1_1") (pintype "passive"))
      (node (ref "1A-HUB1") (pin "1") (pinfunction "KL_1") (pintype "passive"))
    )
    (net (code "18") (name "1MA1-") (class "Default")
      (node (ref "1A") (pin "2") (pinfunction "2_2") (pintype "passive"))
      (node (ref "1A-HUB1") (pin "2") (pinfunction "KL_2") (pintype "passive"))
    )
    (net (code "19") (name "1MA2+") (class "Default")
      (node (ref "1A") (pin "3") (pinfunction "3_3") (pintype "passive"))
      (node (ref "1A-HUB2") (pin "1") (pinfunction "KL_1") (pintype "passive"))
    )
    (net (code "20") (name "1MA2-") (class "Default")
      (node (ref "1A") (pin "4") (pinfunction "4_4") (pintype "passive"))
      (node (ref "1A-HUB2") (pin "2") (pinfunction "KL_2") (pintype "passive"))
    )
    (net (code "21") (name "1MA3+") (class "Default")
      (node (ref "1A") (pin "5") (pinfunction "5_5") (pintype "passive"))
      (node (ref "1A-HUB3") (pin "2") (pinfunction "KL_2") (pintype "passive"))
    )
    (net (code "22") (name "1MA3-") (class "Default")
      (node (ref "1A") (pin "6") (pinfunction "6_6") (pintype "passive"))
      (node (ref "1A-HUB3") (pin "1") (pinfunction "KL_1") (pintype "passive"))
    )
    (net (code "23") (name "1MA4+") (class "Default")
      (node (ref "1A") (pin "7") (pinfunction "7_7") (pintype "passive"))
      (node (ref "1A-HUB4") (pin "2") (pinfunction "KL_2") (pintype "passive"))
    )
    (net (code "24") (name "1MA4-") (class "Default")
      (node (ref "1A") (pin "8") (pinfunction "8_8") (pintype "passive"))
      (node (ref "1A-HUB4") (pin "1") (pinfunction "KL_1") (pintype "passive"))
    )
    (net (code "25") (name "2LC1+") (class "Default")
      (node (ref "2C") (pin "1") (pinfunction "1_1") (pintype "passive"))
      (node (ref "2C-HUB1") (pin "2") (pinfunction "KL_2") (pintype "passive"))
    )
    (net (code "26") (name "2LC1-") (class "Default")
      (node (ref "2C") (pin "2") (pinfunction "2_2") (pintype "passive"))
      (node (ref "2C-HUB1") (pin "1") (pinfunction "KL_1") (pintype "passive"))
    )
    (net (code "27") (name "2LC2+") (class "Default")
      (node (ref "2C") (pin "3") (pinfunction "3_3") (pintype "passive"))
      (node (ref "2C-HUB2") (pin "2") (pinfunction "KL_2") (pintype "passive"))
    )
    (net (code "28") (name "2LC2-") (class "Default")
      (node (ref "2C") (pin "4") (pinfunction "4_4") (pintype "passive"))
      (node (ref "2C-HUB2") (pin "1") (pinfunction "KL_1") (pintype "passive"))
    )
    (net (code "29") (name "2LC3+") (class "Default")
      (node (ref "2C") (pin "5") (pinfunction "5_5") (pintype "passive"))
      (node (ref "2C-HUB3") (pin "2") (pinfunction "KL_2") (pintype "passive"))
    )
    (net (code "30") (name "2LC3-") (class "Default")
      (node (ref "2C") (pin "6") (pinfunction "6_6") (pintype "passive"))
      (node (ref "2C-HUB3") (pin "1") (pinfunction "KL_1") (pintype "passive"))
    )
    (net (code "31") (name "2LC4+") (class "Default")
      (node (ref "2C") (pin "7") (pinfunction "7_7") (pintype "passive"))
      (node (ref "2C-HUB4") (pin "2") (pinfunction "KL_2") (pintype "passive"))
    )
    (net (code "32") (name "2LC4-") (class "Default")
      (node (ref "2C") (pin "8") (pinfunction "8_8") (pintype "passive"))
      (node (ref "2C-HUB4") (pin "1") (pinfunction "KL_1") (pintype "passive"))
    )
    (net (code "33") (name "2LD1+") (class "Default")
      (node (ref "2D") (pin "1") (pinfunction "1_1") (pintype "passive"))
      (node (ref "2D-HUB1") (pin "1") (pinfunction "KL_1") (pintype "passive"))
    )
    (net (code "34") (name "2LD1-") (class "Default")
      (node (ref "2D") (pin "2") (pinfunction "2_2") (pintype "passive"))
      (node (ref "2D-HUB1") (pin "2") (pinfunction "KL_2") (pintype "passive"))
    )
    (net (code "35") (name "2LD2+") (class "Default")
      (node (ref "2D") (pin "3") (pinfunction "3_3") (pintype "passive"))
      (node (ref "2D-HUB2") (pin "2") (pinfunction "KL_2") (pintype "passive"))
    )
    (net (code "36") (name "2LD2-") (class "Default")
      (node (ref "2D") (pin "4") (pinfunction "4_4") (pintype "passive"))
      (node (ref "2D-HUB2") (pin "1") (pinfunction "KL_1") (pintype "passive"))
    )
    (net (code "37") (name "2LD3+") (class "Default")
      (node (ref "2D") (pin "5") (pinfunction "5_5") (pintype "passive"))
      (node (ref "2D-HUB3") (pin "2") (pinfunction "KL_2") (pintype "passive"))
    )
    (net (code "38") (name "2LD3-") (class "Default")
      (node (ref "2D") (pin "6") (pinfunction "6_6") (pintype "passive"))
      (node (ref "2D-HUB3") (pin "1") (pinfunction "KL_1") (pintype "passive"))
    )
    (net (code "39") (name "2MA1+") (class "Default")
      (node (ref "2A") (pin "1") (pinfunction "1_1") (pintype "passive"))
      (node (ref "2A-HUB1") (pin "2") (pinfunction "KL_2") (pintype "passive"))
    )
    (net (code "40") (name "2MA1-") (class "Default")
      (node (ref "2A") (pin "2") (pinfunction "2_2") (pintype "passive"))
      (node (ref "2A-HUB1") (pin "1") (pinfunction "KL_1") (pintype "passive"))
    )
    (net (code "41") (name "2MA2+") (class "Default")
      (node (ref "2A") (pin "3") (pinfunction "3_3") (pintype "passive"))
      (node (ref "2A-HUB2") (pin "2") (pinfunction "KL_2") (pintype "passive"))
    )
    (net (code "42") (name "2MA2-") (class "Default")
      (node (ref "2A") (pin "4") (pinfunction "4_4") (pintype "passive"))
      (node (ref "2A-HUB2") (pin "1") (pinfunction "KL_1") (pintype "passive"))
    )
    (net (code "43") (name "2MA3+") (class "Default")
      (node (ref "2A") (pin "5") (pinfunction "5_5") (pintype "passive"))
      (node (ref "2A-HUB3") (pin "2") (pinfunction "KL_2") (pintype "passive"))
    )
    (net (code "44") (name "2MA3-") (class "Default")
      (node (ref "2A") (pin "6") (pinfunction "6_6") (pintype "passive"))
      (node (ref "2A-HUB3") (pin "1") (pinfunction "KL_1") (pintype "passive"))
    )
    (net (code "45") (name "2MA4+") (class "Default")
      (node (ref "2A") (pin "7") (pinfunction "7_7") (pintype "passive"))
      (node (ref "2A-HUB4") (pin "2") (pinfunction "KL_2") (pintype "passive"))
    )
    (net (code "46") (name "2MA4-") (class "Default")
      (node (ref "2A") (pin "8") (pinfunction "8_8") (pintype "passive"))
      (node (ref "2A-HUB4") (pin "1") (pinfunction "KL_1") (pintype "passive"))
    )
    (net (code "47") (name "2MB1+") (class "Default")
      (node (ref "2B") (pin "1") (pinfunction "1_1") (pintype "passive"))
      (node (ref "2B-HUB1") (pin "2") (pinfunction "KL_2") (pintype "passive"))
    )
    (net (code "48") (name "2MB1-") (class "Default")
      (node (ref "2B") (pin "2") (pinfunction "2_2") (pintype "passive"))
      (node (ref "2B-HUB1") (pin "1") (pinfunction "KL_1") (pintype "passive"))
    )
    (net (code "49") (name "2MB2+") (class "Default")
      (node (ref "2B") (pin "3") (pinfunction "3_3") (pintype "passive"))
      (node (ref "2B-HUB2") (pin "2") (pinfunction "KL_2") (pintype "passive"))
    )
    (net (code "50") (name "2MB2-") (class "Default")
      (node (ref "2B") (pin "4") (pinfunction "4_4") (pintype "passive"))
      (node (ref "2B-HUB2") (pin "1") (pinfunction "KL_1") (pintype "passive"))
    )
    (net (code "51") (name "2MB3+") (class "Default")
      (node (ref "2B") (pin "5") (pinfunction "5_5") (pintype "passive"))
      (node (ref "2B-HUB3") (pin "2") (pinfunction "KL_2") (pintype "passive"))
    )
    (net (code "52") (name "2MB3-") (class "Default")
      (node (ref "2B") (pin "6") (pinfunction "6_6") (pintype "passive"))
      (node (ref "2B-HUB3") (pin "1") (pinfunction "KL_1") (pintype "passive"))
    )
    (net (code "53") (name "2MB4+") (class "Default")
      (node (ref "2B") (pin "7") (pinfunction "7_7") (pintype "passive"))
      (node (ref "2B-HUB4") (pin "2") (pinfunction "KL_2") (pintype "passive"))
    )
    (net (code "54") (name "2MB4-") (class "Default")
      (node (ref "2B") (pin "8") (pinfunction "8_8") (pintype "passive"))
      (node (ref "2B-HUB4") (pin "1") (pinfunction "KL_1") (pintype "passive"))
    )
    (net (code "55") (name "3A_5VM") (class "Default")
      (node (ref "3A") (pin "5") (pinfunction "5_5") (pintype "passive"))
      (node (ref "3A_HUB2") (pin "2") (pinfunction "2_2") (pintype "passive"))
      (node (ref "3A_HUB3") (pin "2") (pinfunction "2_2") (pintype "passive"))
    )
    (net (code "56") (name "3A_GND") (class "Default")
      (node (ref "3A") (pin "8") (pinfunction "8_8") (pintype "passive"))
      (node (ref "3A_HUB2") (pin "1") (pinfunction "1_1") (pintype "passive"))
      (node (ref "3A_HUB3") (pin "1") (pinfunction "1_1") (pintype "passive"))
    )
    (net (code "57") (name "3C_5V") (class "Default")
      (node (ref "3C") (pin "1") (pinfunction "1_1") (pintype "passive"))
      (node (ref "3C_HUB1") (pin "1") (pinfunction "1_1") (pintype "passive"))
      (node (ref "3C_HUB2") (pin "1") (pinfunction "1_1") (pintype "passive"))
    )
    (net (code "58") (name "3C_GND") (class "Default")
      (node (ref "3C") (pin "8") (pinfunction "8_8") (pintype "passive"))
      (node (ref "3C_HUB1") (pin "2") (pinfunction "2_2") (pintype "passive"))
      (node (ref "3C_HUB2") (pin "2") (pinfunction "2_2") (pintype "passive"))
    )
    (net (code "59") (name "3MA1+") (class "Default")
      (node (ref "3A") (pin "1") (pinfunction "1_1") (pintype "passive"))
      (node (ref "3A-HUB1") (pin "1") (pinfunction "KL_1") (pintype "passive"))
    )
    (net (code "60") (name "3MA1-") (class "Default")
      (node (ref "3A") (pin "2") (pinfunction "2_2") (pintype "passive"))
      (node (ref "3A-HUB1") (pin "2") (pinfunction "KL_2") (pintype "passive"))
    )
    (net (code "61") (name "3MB1+") (class "Default")
      (node (ref "3B") (pin "1") (pinfunction "1_1") (pintype "passive"))
      (node (ref "3B-HUB1") (pin "1") (pinfunction "KL_1") (pintype "passive"))
    )
    (net (code "62") (name "3MB1-") (class "Default")
      (node (ref "3B") (pin "2") (pinfunction "2_2") (pintype "passive"))
      (node (ref "3B-HUB1") (pin "2") (pinfunction "KL_2") (pintype "passive"))
    )
    (net (code "63") (name "3MB2+") (class "Default")
      (node (ref "3B") (pin "3") (pinfunction "3_3") (pintype "passive"))
      (node (ref "3B-HUB2") (pin "2") (pinfunction "KL_2") (pintype "passive"))
    )
    (net (code "64") (name "3MB2-") (class "Default")
      (node (ref "3B") (pin "4") (pinfunction "4_4") (pintype "passive"))
      (node (ref "3B-HUB2") (pin "1") (pinfunction "KL_1") (pintype "passive"))
    )
    (net (code "65") (name "3P2") (class "Default")
      (node (ref "3C") (pin "2") (pinfunction "2_2") (pintype "passive"))
      (node (ref "3C_HUB1") (pin "3") (pinfunction "3_3") (pintype "passive"))
    )
    (net (code "66") (name "3P3") (class "Default")
      (node (ref "3C") (pin "3") (pinfunction "3_3") (pintype "passive"))
      (node (ref "3C_HUB2") (pin "3") (pinfunction "3_3") (pintype "passive"))
    )
    (net (code "67") (name "3P7") (class "Default")
      (node (ref "3A") (pin "6") (pinfunction "6_6") (pintype "passive"))
      (node (ref "3A_HUB2") (pin "3") (pinfunction "3_3") (pintype "passive"))
    )
    (net (code "68") (name "3P8") (class "Default")
      (node (ref "3A") (pin "7") (pinfunction "7_7") (pintype "passive"))
      (node (ref "3A_HUB3") (pin "3") (pinfunction "3_3") (pintype "passive"))
    )
    (net (code "69") (name "4LC1+") (class "Default")
      (node (ref "4C") (pin "1") (pinfunction "1_1") (pintype "passive"))
      (node (ref "4C-HUB1") (pin "1") (pinfunction "KL_1") (pintype "passive"))
    )
    (net (code "70") (name "4LC1-") (class "Default")
      (node (ref "4C") (pin "2") (pinfunction "2_2") (pintype "passive"))
      (node (ref "4C-HUB1") (pin "2") (pinfunction "KL_2") (pintype "passive"))
    )
    (net (code "71") (name "4LC2+") (class "Default")
      (node (ref "4C") (pin "3") (pinfunction "3_3") (pintype "passive"))
      (node (ref "4C-HUB2") (pin "1") (pinfunction "KL_1") (pintype "passive"))
    )
    (net (code "72") (name "4LC2-") (class "Default")
      (node (ref "4C") (pin "4") (pinfunction "4_4") (pintype "passive"))
      (node (ref "4C-HUB2") (pin "2") (pinfunction "KL_2") (pintype "passive"))
    )
    (net (code "73") (name "4LC3+") (class "Default")
      (node (ref "4C") (pin "5") (pinfunction "5_5") (pintype "passive"))
      (node (ref "4C-HUB3") (pin "2") (pinfunction "KL_2") (pintype "passive"))
    )
    (net (code "74") (name "4LC3-") (class "Default")
      (node (ref "4C") (pin "6") (pinfunction "6_6") (pintype "passive"))
      (node (ref "4C-HUB3") (pin "1") (pinfunction "KL_1") (pintype "passive"))
    )
    (net (code "75") (name "4LC4+") (class "Default")
      (node (ref "4C") (pin "7") (pinfunction "7_7") (pintype "passive"))
      (node (ref "4C-HUB4") (pin "2") (pinfunction "KL_2") (pintype "passive"))
    )
    (net (code "76") (name "4LC4-") (class "Default")
      (node (ref "4C") (pin "8") (pinfunction "8_8") (pintype "passive"))
      (node (ref "4C-HUB4") (pin "1") (pinfunction "KL_1") (pintype "passive"))
    )
    (net (code "77") (name "4MA1+") (class "Default")
      (node (ref "4A") (pin "1") (pinfunction "1_1") (pintype "passive"))
      (node (ref "4A-HUB1") (pin "1") (pinfunction "KL_1") (pintype "passive"))
    )
    (net (code "78") (name "4MA1-") (class "Default")
      (node (ref "4A") (pin "2") (pinfunction "2_2") (pintype "passive"))
      (node (ref "4A-HUB1") (pin "2") (pinfunction "KL_2") (pintype "passive"))
    )
    (net (code "79") (name "4MA2+") (class "Default")
      (node (ref "4A") (pin "3") (pinfunction "3_3") (pintype "passive"))
      (node (ref "4A-HUB2") (pin "1") (pinfunction "KL_1") (pintype "passive"))
    )
    (net (code "80") (name "4MA2-") (class "Default")
      (node (ref "4A") (pin "4") (pinfunction "4_4") (pintype "passive"))
      (node (ref "4A-HUB2") (pin "2") (pinfunction "KL_2") (pintype "passive"))
    )
    (net (code "81") (name "4MA3+") (class "Default")
      (node (ref "4A") (pin "5") (pinfunction "5_5") (pintype "passive"))
      (node (ref "4A-HUB3") (pin "2") (pinfunction "KL_2") (pintype "passive"))
    )
    (net (code "82") (name "4MA3-") (class "Default")
      (node (ref "4A") (pin "6") (pinfunction "6_6") (pintype "passive"))
      (node (ref "4A-HUB3") (pin "1") (pinfunction "KL_1") (pintype "passive"))
    )
    (net (code "83") (name "4MB1+") (class "Default")
      (node (ref "4B") (pin "1") (pinfunction "1_1") (pintype "passive"))
      (node (ref "4B-HUB1") (pin "1") (pinfunction "KL_1") (pintype "passive"))
    )
    (net (code "84") (name "4MB1-") (class "Default")
      (node (ref "4B") (pin "2") (pinfunction "2_2") (pintype "passive"))
      (node (ref "4B-HUB1") (pin "2") (pinfunction "KL_2") (pintype "passive"))
    )
    (net (code "85") (name "4MB2+") (class "Default")
      (node (ref "4B") (pin "3") (pinfunction "3_3") (pintype "passive"))
      (node (ref "4B-HUB2") (pin "1") (pinfunction "KL_1") (pintype "passive"))
    )
    (net (code "86") (name "4MB2-") (class "Default")
      (node (ref "4B") (pin "4") (pinfunction "4_4") (pintype "passive"))
      (node (ref "4B-HUB2") (pin "2") (pinfunction "KL_2") (pintype "passive"))
    )
    (net (code "87") (name "4MB3+") (class "Default")
      (node (ref "4B") (pin "5") (pinfunction "5_5") (pintype "passive"))
      (node (ref "4B-HUB3") (pin "2") (pinfunction "KL_2") (pintype "passive"))
    )
    (net (code "88") (name "4MB3-") (class "Default")
      (node (ref "4B") (pin "6") (pinfunction "6_6") (pintype "passive"))
      (node (ref "4B-HUB3") (pin "1") (pinfunction "KL_1") (pintype "passive"))
    )
    (net (code "89") (name "4MB4+") (class "Default")
      (node (ref "4B") (pin "7") (pinfunction "7_7") (pintype "passive"))
      (node (ref "4B-HUB4") (pin "2") (pinfunction "KL_2") (pintype "passive"))
    )
    (net (code "90") (name "4MB4-") (class "Default")
      (node (ref "4B") (pin "8") (pinfunction "8_8") (pintype "passive"))
      (node (ref "4B-HUB4") (pin "1") (pinfunction "KL_1") (pintype "passive"))
    )
    (net (code "91") (name "5C_5VM") (class "Default")
      (node (ref "5C") (pin "4") (pinfunction "4_4") (pintype "passive"))
      (node (ref "5C-HUB1") (pin "2") (pinfunction "KL_2") (pintype "passive"))
      (node (ref "5C-HUB2") (pin "2") (pinfunction "KL_2") (pintype "passive"))
      (node (ref "5C-HUB3") (pin "2") (pinfunction "KL_2") (pintype "passive"))
    )
    (net (code "92") (name "5C_GND") (class "Default")
      (node (ref "5C") (pin "8") (pinfunction "8_8") (pintype "passive"))
      (node (ref "5C-HUB1") (pin "1") (pinfunction "KL_1") (pintype "passive"))
      (node (ref "5C-HUB2") (pin "1") (pinfunction "KL_1") (pintype "passive"))
      (node (ref "5C-HUB3") (pin "1") (pinfunction "KL_1") (pintype "passive"))
    )
    (net (code "93") (name "5D_5V1") (class "Default")
      (node (ref "5D") (pin "1") (pinfunction "1_1") (pintype "passive"))
      (node (ref "5D_HUB1") (pin "1") (pinfunction "1_1") (pintype "passive"))
      (node (ref "5D_HUB2") (pin "1") (pinfunction "1_1") (pintype "passive"))
    )
    (net (code "94") (name "5D_5V2") (class "Default")
      (node (ref "5D") (pin "4") (pinfunction "4_4") (pintype "passive"))
      (node (ref "5D_HUB3") (pin "1") (pinfunction "1_1") (pintype "passive"))
      (node (ref "5D_HUB4") (pin "1") (pinfunction "1_1") (pintype "passive"))
    )
    (net (code "95") (name "5D_GND") (class "Default")
      (node (ref "5D") (pin "8") (pinfunction "8_8") (pintype "passive"))
      (node (ref "5D_HUB1") (pin "2") (pinfunction "2_2") (pintype "passive"))
      (node (ref "5D_HUB2") (pin "2") (pinfunction "2_2") (pintype "passive"))
      (node (ref "5D_HUB3") (pin "2") (pinfunction "2_2") (pintype "passive"))
      (node (ref "5D_HUB4") (pin "2") (pinfunction "2_2") (pintype "passive"))
    )
    (net (code "96") (name "5MA1+") (class "Default")
      (node (ref "5A") (pin "1") (pinfunction "1_1") (pintype "passive"))
      (node (ref "5A-HU1") (pin "1") (pinfunction "KL_1") (pintype "passive"))
    )
    (net (code "97") (name "5MA1-") (class "Default")
      (node (ref "5A") (pin "2") (pinfunction "2_2") (pintype "passive"))
      (node (ref "5A-HU1") (pin "2") (pinfunction "KL_2") (pintype "passive"))
    )
    (net (code "98") (name "5MB1+") (class "Default")
      (node (ref "5B") (pin "1") (pinfunction "1_1") (pintype "passive"))
      (node (ref "5B-HUB1") (pin "1") (pinfunction "KL_1") (pintype "passive"))
    )
    (net (code "99") (name "5MB1-") (class "Default")
      (node (ref "5B") (pin "2") (pinfunction "2_2") (pintype "passive"))
      (node (ref "5B-HUB1") (pin "2") (pinfunction "KL_2") (pintype "passive"))
    )
    (net (code "100") (name "5P2") (class "Default")
      (node (ref "5D") (pin "2") (pinfunction "2_2") (pintype "passive"))
      (node (ref "5D_HUB1") (pin "3") (pinfunction "3_3") (pintype "passive"))
    )
    (net (code "101") (name "5P3") (class "Default")
      (node (ref "5D") (pin "3") (pinfunction "3_3") (pintype "passive"))
      (node (ref "5D_HUB2") (pin "3") (pinfunction "3_3") (pintype "passive"))
    )
    (net (code "102") (name "5P4") (class "Default")
      (node (ref "5D") (pin "5") (pinfunction "5_5") (pintype "passive"))
      (node (ref "5D_HUB3") (pin "3") (pinfunction "3_3") (pintype "passive"))
    )
    (net (code "103") (name "5P5") (class "Default")
      (node (ref "5D") (pin "6") (pinfunction "6_6") (pintype "passive"))
      (node (ref "5D_HUB4") (pin "3") (pinfunction "3_3") (pintype "passive"))
    )
    (net (code "104") (name "5P6") (class "Default")
      (node (ref "5C") (pin "5") (pinfunction "5_5") (pintype "passive"))
      (node (ref "5C-HUB1") (pin "3") (pinfunction "KL_3") (pintype "passive"))
    )
    (net (code "105") (name "5P7") (class "Default")
      (node (ref "5C") (pin "6") (pinfunction "6_6") (pintype "passive"))
      (node (ref "5C-HUB2") (pin "3") (pinfunction "KL_3") (pintype "passive"))
    )
    (net (code "106") (name "5P8") (class "Default")
      (node (ref "5C") (pin "7") (pinfunction "7_7") (pintype "passive"))
      (node (ref "5C-HUB3") (pin "3") (pinfunction "KL_3") (pintype "passive"))
    )
    (net (code "107") (name "6A_5VM") (class "Default")
      (node (ref "6A") (pin "5") (pinfunction "5_5") (pintype "passive"))
      (node (ref "6A-HUB1") (pin "2") (pinfunction "KL_2") (pintype "passive"))
      (node (ref "6A-HUB2") (pin "2") (pinfunction "KL_2") (pintype "passive"))
    )
    (net (code "108") (name "6A_GND") (class "Default")
      (node (ref "6A") (pin "8") (pinfunction "8_8") (pintype "passive"))
      (node (ref "6A-HUB1") (pin "1") (pinfunction "KL_1") (pintype "passive"))
      (node (ref "6A-HUB2") (pin "1") (pinfunction "KL_1") (pintype "passive"))
    )
    (net (code "109") (name "6B_5V1") (class "Default")
      (node (ref "6B") (pin "1") (pinfunction "1_1") (pintype "passive"))
      (node (ref "6B_HUB1") (pin "1") (pinfunction "1_1") (pintype "passive"))
      (node (ref "6B_HUB2") (pin "1") (pinfunction "1_1") (pintype "passive"))
    )
    (net (code "110") (name "6B_5V2") (class "Default")
      (node (ref "6B") (pin "4") (pinfunction "4_4") (pintype "passive"))
      (node (ref "6B_HUB3") (pin "1") (pinfunction "1_1") (pintype "passive"))
      (node (ref "6B_HUB4") (pin "1") (pinfunction "1_1") (pintype "passive"))
    )
    (net (code "111") (name "6B_GND") (class "Default")
      (node (ref "6B") (pin "8") (pinfunction "8_8") (pintype "passive"))
      (node (ref "6B_HUB1") (pin "2") (pinfunction "2_2") (pintype "passive"))
      (node (ref "6B_HUB2") (pin "2") (pinfunction "2_2") (pintype "passive"))
      (node (ref "6B_HUB3") (pin "2") (pinfunction "2_2") (pintype "passive"))
      (node (ref "6B_HUB4") (pin "2") (pinfunction "2_2") (pintype "passive"))
    )
    (net (code "112") (name "6P2") (class "Default")
      (node (ref "6B") (pin "2") (pinfunction "2_2") (pintype "passive"))
      (node (ref "6B_HUB1") (pin "3") (pinfunction "3_3") (pintype "passive"))
    )
    (net (code "113") (name "6P3") (class "Default")
      (node (ref "6B") (pin "3") (pinfunction "3_3") (pintype "passive"))
      (node (ref "6B_HUB2") (pin "3") (pinfunction "3_3") (pintype "passive"))
    )
    (net (code "114") (name "6P4") (class "Default")
      (node (ref "6B") (pin "5") (pinfunction "5_5") (pintype "passive"))
      (node (ref "6B_HUB3") (pin "3") (pinfunction "3_3") (pintype "passive"))
    )
    (net (code "115") (name "6P5") (class "Default")
      (node (ref "6B") (pin "6") (pinfunction "6_6") (pintype "passive"))
      (node (ref "6B_HUB4") (pin "3") (pinfunction "3_3") (pintype "passive"))
    )
    (net (code "116") (name "6P6") (class "Default")
      (node (ref "6A") (pin "6") (pinfunction "6_6") (pintype "passive"))
      (node (ref "6A-HUB1") (pin "3") (pinfunction "KL_3") (pintype "passive"))
    )
    (net (code "117") (name "6P7") (class "Default")
      (node (ref "6A") (pin "7") (pinfunction "7_7") (pintype "passive"))
      (node (ref "6A-HUB2") (pin "3") (pinfunction "KL_3") (pintype "passive"))
    )
    (net (code "118") (name "7D_5VM") (class "Default")
      (node (ref "7D") (pin "5") (pinfunction "5_5") (pintype "passive"))
      (node (ref "7D_HUB1") (pin "2") (pinfunction "2_2") (pintype "passive"))
      (node (ref "7D_HUB2") (pin "2") (pinfunction "2_2") (pintype "passive"))
    )
    (net (code "119") (name "7D_GND") (class "Default")
      (node (ref "7D") (pin "8") (pinfunction "8_8") (pintype "passive"))
      (node (ref "7D_HUB1") (pin "1") (pinfunction "1_1") (pintype "passive"))
      (node (ref "7D_HUB2") (pin "1") (pinfunction "1_1") (pintype "passive"))
    )
    (net (code "120") (name "7LB1+") (class "Default")
      (node (ref "7B") (pin "1") (pinfunction "1_1") (pintype "passive"))
      (node (ref "7B-HUB1") (pin "1") (pinfunction "KL_1") (pintype "passive"))
    )
    (net (code "121") (name "7LB1-") (class "Default")
      (node (ref "7B") (pin "2") (pinfunction "2_2") (pintype "passive"))
      (node (ref "7B-HUB1") (pin "2") (pinfunction "KL_2") (pintype "passive"))
    )
    (net (code "122") (name "7LB2+") (class "Default")
      (node (ref "7B") (pin "3") (pinfunction "3_3") (pintype "passive"))
      (node (ref "7B-HUB2") (pin "1") (pinfunction "KL_1") (pintype "passive"))
    )
    (net (code "123") (name "7LB2-") (class "Default")
      (node (ref "7B") (pin "4") (pinfunction "4_4") (pintype "passive"))
      (node (ref "7B-HUB2") (pin "2") (pinfunction "KL_2") (pintype "passive"))
    )
    (net (code "124") (name "7LB3+") (class "Default")
      (node (ref "7B") (pin "5") (pinfunction "5_5") (pintype "passive"))
      (node (ref "7B-HUB3") (pin "2") (pinfunction "KL_2") (pintype "passive"))
    )
    (net (code "125") (name "7LB3-") (class "Default")
      (node (ref "7B") (pin "6") (pinfunction "6_6") (pintype "passive"))
      (node (ref "7B-HUB3") (pin "1") (pinfunction "KL_1") (pintype "passive"))
    )
    (net (code "126") (name "7LB4+") (class "Default")
      (node (ref "7B") (pin "7") (pinfunction "7_7") (pintype "passive"))
      (node (ref "7B-HUB4") (pin "2") (pinfunction "KL_2") (pintype "passive"))
    )
    (net (code "127") (name "7LB4-") (class "Default")
      (node (ref "7B") (pin "8") (pinfunction "8_8") (pintype "passive"))
      (node (ref "7B-HUB4") (pin "1") (pinfunction "KL_1") (pintype "passive"))
    )
    (net (code "128") (name "7LC1+") (class "Default")
      (node (ref "7C") (pin "1") (pinfunction "1_1") (pintype "passive"))
      (node (ref "7C-HUB1") (pin "1") (pinfunction "KL_1") (pintype "passive"))
    )
    (net (code "129") (name "7LC1-") (class "Default")
      (node (ref "7C") (pin "2") (pinfunction "2_2") (pintype "passive"))
      (node (ref "7C-HUB1") (pin "2") (pinfunction "KL_2") (pintype "passive"))
    )
    (net (code "130") (name "7LC2+") (class "Default")
      (node (ref "7C") (pin "3") (pinfunction "3_3") (pintype "passive"))
      (node (ref "7C-HUB2") (pin "1") (pinfunction "KL_1") (pintype "passive"))
    )
    (net (code "131") (name "7LC2-") (class "Default")
      (node (ref "7C") (pin "4") (pinfunction "4_4") (pintype "passive"))
      (node (ref "7C-HUB2") (pin "2") (pinfunction "KL_2") (pintype "passive"))
    )
    (net (code "132") (name "7LC3+") (class "Default")
      (node (ref "7C") (pin "5") (pinfunction "5_5") (pintype "passive"))
      (node (ref "7C-HUB3") (pin "2") (pinfunction "KL_2") (pintype "passive"))
    )
    (net (code "133") (name "7LC3-") (class "Default")
      (node (ref "7C") (pin "6") (pinfunction "6_6") (pintype "passive"))
      (node (ref "7C-HUB3") (pin "1") (pinfunction "KL_1") (pintype "passive"))
    )
    (net (code "134") (name "7LC4+") (class "Default")
      (node (ref "7C") (pin "7") (pinfunction "7_7") (pintype "passive"))
      (node (ref "7C-HUB4") (pin "2") (pinfunction "KL_2") (pintype "passive"))
    )
    (net (code "135") (name "7LC4-") (class "Default")
      (node (ref "7C") (pin "8") (pinfunction "8_8") (pintype "passive"))
      (node (ref "7C-HUB4") (pin "1") (pinfunction "KL_1") (pintype "passive"))
    )
    (net (code "136") (name "7MA1+") (class "Default")
      (node (ref "7A") (pin "1") (pinfunction "1_1") (pintype "passive"))
      (node (ref "7A-HUB1") (pin "1") (pinfunction "KL_1") (pintype "passive"))
    )
    (net (code "137") (name "7MA1-") (class "Default")
      (node (ref "7A") (pin "2") (pinfunction "2_2") (pintype "passive"))
      (node (ref "7A-HUB1") (pin "2") (pinfunction "KL_2") (pintype "passive"))
    )
    (net (code "138") (name "7MA2+") (class "Default")
      (node (ref "7A") (pin "3") (pinfunction "3_3") (pintype "passive"))
      (node (ref "7A-HUB2") (pin "2") (pinfunction "KL_2") (pintype "passive"))
    )
    (net (code "139") (name "7MA2-") (class "Default")
      (node (ref "7A") (pin "4") (pinfunction "4_4") (pintype "passive"))
      (node (ref "7A-HUB2") (pin "1") (pinfunction "KL_1") (pintype "passive"))
    )
    (net (code "140") (name "7P45") (class "Default")
      (node (ref "7D") (pin "7") (pinfunction "7_7") (pintype "passive"))
      (node (ref "7D_HUB2") (pin "3") (pinfunction "3_3") (pintype "passive"))
    )
    (net (code "141") (name "7P46") (class "Default")
      (node (ref "7D") (pin "6") (pinfunction "6_6") (pintype "passive"))
      (node (ref "7D_HUB1") (pin "3") (pinfunction "3_3") (pintype "passive"))
    )
    (net (code "142") (name "8C_5V1") (class "Default")
      (node (ref "8C") (pin "1") (pinfunction "1_1") (pintype "passive"))
      (node (ref "8C_HUB1") (pin "1") (pinfunction "1_1") (pintype "passive"))
    )
    (net (code "143") (name "8C_5V2") (class "Default")
      (node (ref "8C") (pin "3") (pinfunction "3_3") (pintype "passive"))
      (node (ref "8C_HUB2") (pin "1") (pinfunction "1_1") (pintype "passive"))
    )
    (net (code "144") (name "8C_5V3") (class "Default")
      (node (ref "8C") (pin "5") (pinfunction "5_5") (pintype "passive"))
      (node (ref "8C_HUB3") (pin "1") (pinfunction "1_1") (pintype "passive"))
    )
    (net (code "145") (name "8C_GND") (class "Default")
      (node (ref "8C") (pin "8") (pinfunction "8_8") (pintype "passive"))
      (node (ref "8C_HUB1") (pin "2") (pinfunction "2_2") (pintype "passive"))
      (node (ref "8C_HUB2") (pin "2") (pinfunction "2_2") (pintype "passive"))
      (node (ref "8C_HUB3") (pin "2") (pinfunction "2_2") (pintype "passive"))
    )
    (net (code "146") (name "8FB1+") (class "Default")
      (node (ref "8B") (pin "1") (pinfunction "1_1") (pintype "passive"))
      (node (ref "8B-HUB1") (pin "1") (pinfunction "KL_1") (pintype "passive"))
    )
    (net (code "147") (name "8FB1-") (class "Default")
      (node (ref "8B") (pin "2") (pinfunction "2_2") (pintype "passive"))
      (node (ref "8B-HUB1") (pin "2") (pinfunction "KL_2") (pintype "passive"))
    )
    (net (code "148") (name "8FB2+") (class "Default")
      (node (ref "8B") (pin "3") (pinfunction "3_3") (pintype "passive"))
      (node (ref "8B-HUB2") (pin "1") (pinfunction "KL_1") (pintype "passive"))
    )
    (net (code "149") (name "8FB2-") (class "Default")
      (node (ref "8B") (pin "4") (pinfunction "4_4") (pintype "passive"))
      (node (ref "8B-HUB2") (pin "2") (pinfunction "KL_2") (pintype "passive"))
    )
    (net (code "150") (name "8FB3+") (class "Default")
      (node (ref "8B") (pin "5") (pinfunction "5_5") (pintype "passive"))
      (node (ref "8B-HUB3") (pin "2") (pinfunction "KL_2") (pintype "passive"))
    )
    (net (code "151") (name "8FB3-") (class "Default")
      (node (ref "8B") (pin "6") (pinfunction "6_6") (pintype "passive"))
      (node (ref "8B-HUB3") (pin "1") (pinfunction "KL_1") (pintype "passive"))
    )
    (net (code "152") (name "8MA1+") (class "Default")
      (node (ref "8A") (pin "1") (pinfunction "1_1") (pintype "passive"))
      (node (ref "8A-HU1") (pin "1") (pinfunction "KL_1") (pintype "passive"))
    )
    (net (code "153") (name "8MA1-") (class "Default")
      (node (ref "8A") (pin "2") (pinfunction "2_2") (pintype "passive"))
      (node (ref "8A-HU1") (pin "2") (pinfunction "KL_2") (pintype "passive"))
    )
    (net (code "154") (name "8MA2+") (class "Default")
      (node (ref "8A") (pin "3") (pinfunction "3_3") (pintype "passive"))
      (node (ref "8A-HU2") (pin "1") (pinfunction "KL_1") (pintype "passive"))
    )
    (net (code "155") (name "8MA2-") (class "Default")
      (node (ref "8A") (pin "4") (pinfunction "4_4") (pintype "passive"))
      (node (ref "8A-HU2") (pin "2") (pinfunction "KL_2") (pintype "passive"))
    )
    (net (code "156") (name "8MA3+") (class "Default")
      (node (ref "8A") (pin "5") (pinfunction "5_5") (pintype "passive"))
      (node (ref "8A-HU3") (pin "2") (pinfunction "KL_2") (pintype "passive"))
    )
    (net (code "157") (name "8MA3-") (class "Default")
      (node (ref "8A") (pin "6") (pinfunction "6_6") (pintype "passive"))
      (node (ref "8A-HU3") (pin "1") (pinfunction "KL_1") (pintype "passive"))
    )
    (net (code "158") (name "8P44") (class "Default")
      (node (ref "8C") (pin "6") (pinfunction "6_6") (pintype "passive"))
      (node (ref "8C_HUB3") (pin "3") (pinfunction "3_3") (pintype "passive"))
    )
    (net (code "159") (name "8P45") (class "Default")
      (node (ref "8C") (pin "4") (pinfunction "4_4") (pintype "passive"))
      (node (ref "8C_HUB2") (pin "3") (pinfunction "3_3") (pintype "passive"))
    )
    (net (code "160") (name "8P46") (class "Default")
      (node (ref "8C") (pin "2") (pinfunction "2_2") (pintype "passive"))
      (node (ref "8C_HUB1") (pin "3") (pinfunction "3_3") (pintype "passive"))
    )
    (net (code "161") (name "9LA1+") (class "Default")
      (node (ref "9A") (pin "1") (pinfunction "1_1") (pintype "passive"))
      (node (ref "9A-HUB1") (pin "1") (pinfunction "KL_1") (pintype "passive"))
    )
    (net (code "162") (name "9LA1-") (class "Default")
      (node (ref "9A") (pin "2") (pinfunction "2_2") (pintype "passive"))
      (node (ref "9A-HUB1") (pin "2") (pinfunction "KL_2") (pintype "passive"))
    )
    (net (code "163") (name "9LA2+") (class "Default")
      (node (ref "9A") (pin "3") (pinfunction "3_3") (pintype "passive"))
      (node (ref "9A-HUB2") (pin "1") (pinfunction "KL_1") (pintype "passive"))
    )
    (net (code "164") (name "9LA2-") (class "Default")
      (node (ref "9A") (pin "4") (pinfunction "4_4") (pintype "passive"))
      (node (ref "9A-HUB2") (pin "2") (pinfunction "KL_2") (pintype "passive"))
    )
    (net (code "165") (name "9LA3+") (class "Default")
      (node (ref "9A") (pin "5") (pinfunction "5_5") (pintype "passive"))
      (node (ref "9A-HUB3") (pin "2") (pinfunction "KL_2") (pintype "passive"))
    )
    (net (code "166") (name "9LA3-") (class "Default")
      (node (ref "9A") (pin "6") (pinfunction "6_6") (pintype "passive"))
      (node (ref "9A-HUB3") (pin "1") (pinfunction "KL_1") (pintype "passive"))
    )
    (net (code "167") (name "9LA4+") (class "Default")
      (node (ref "9A") (pin "7") (pinfunction "7_7") (pintype "passive"))
      (node (ref "9A-HUB4") (pin "2") (pinfunction "KL_2") (pintype "passive"))
    )
    (net (code "168") (name "9LA4-") (class "Default")
      (node (ref "9A") (pin "8") (pinfunction "8_8") (pintype "passive"))
      (node (ref "9A-HUB4") (pin "1") (pinfunction "KL_1") (pintype "passive"))
    )
    (net (code "169") (name "9LB1+") (class "Default")
      (node (ref "9B") (pin "1") (pinfunction "1_1") (pintype "passive"))
      (node (ref "9B-HUB1") (pin "1") (pinfunction "KL_1") (pintype "passive"))
    )
    (net (code "170") (name "9LB1-") (class "Default")
      (node (ref "9B") (pin "2") (pinfunction "2_2") (pintype "passive"))
      (node (ref "9B-HUB1") (pin "2") (pinfunction "KL_2") (pintype "passive"))
    )
    (net (code "171") (name "9LB2+") (class "Default")
      (node (ref "9B") (pin "3") (pinfunction "3_3") (pintype "passive"))
      (node (ref "9B-HUB2") (pin "1") (pinfunction "KL_1") (pintype "passive"))
    )
    (net (code "172") (name "9LB2-") (class "Default")
      (node (ref "9B") (pin "4") (pinfunction "4_4") (pintype "passive"))
      (node (ref "9B-HUB2") (pin "2") (pinfunction "KL_2") (pintype "passive"))
    )
    (net (code "173") (name "9LB3+") (class "Default")
      (node (ref "9B") (pin "5") (pinfunction "5_5") (pintype "passive"))
      (node (ref "9B-HUB3") (pin "2") (pinfunction "KL_2") (pintype "passive"))
    )
    (net (code "174") (name "9LB3-") (class "Default")
      (node (ref "9B") (pin "6") (pinfunction "6_6") (pintype "passive"))
      (node (ref "9B-HUB3") (pin "1") (pinfunction "KL_1") (pintype "passive"))
    )
    (net (code "175") (name "unconnected-(1B-Pad7)") (class "Default")
      (node (ref "1B") (pin "7") (pinfunction "7_7") (pintype "passive"))
    )
    (net (code "176") (name "unconnected-(1B-Pad8)") (class "Default")
      (node (ref "1B") (pin "8") (pinfunction "8_8") (pintype "passive"))
    )
    (net (code "177") (name "unconnected-(1C-Pad7)") (class "Default")
      (node (ref "1C") (pin "7") (pinfunction "7_7") (pintype "passive"))
    )
    (net (code "178") (name "unconnected-(1C-Pad8)") (class "Default")
      (node (ref "1C") (pin "8") (pinfunction "8_8") (pintype "passive"))
    )
    (net (code "179") (name "unconnected-(1D-Pad5)") (class "Default")
      (node (ref "1D") (pin "5") (pinfunction "5_5") (pintype "passive"))
    )
    (net (code "180") (name "unconnected-(1D-Pad6)") (class "Default")
      (node (ref "1D") (pin "6") (pinfunction "6_6") (pintype "passive"))
    )
    (net (code "181") (name "unconnected-(1D-Pad7)") (class "Default")
      (node (ref "1D") (pin "7") (pinfunction "7_7") (pintype "passive"))
    )
    (net (code "182") (name "unconnected-(1D-Pad8)") (class "Default")
      (node (ref "1D") (pin "8") (pinfunction "8_8") (pintype "passive"))
    )
    (net (code "183") (name "unconnected-(2D-Pad7)") (class "Default")
      (node (ref "2D") (pin "7") (pinfunction "7_7") (pintype "passive"))
    )
    (net (code "184") (name "unconnected-(2D-Pad8)") (class "Default")
      (node (ref "2D") (pin "8") (pinfunction "8_8") (pintype "passive"))
    )
    (net (code "185") (name "unconnected-(3A-Pad3)") (class "Default")
      (node (ref "3A") (pin "3") (pinfunction "3_3") (pintype "passive"))
    )
    (net (code "186") (name "unconnected-(3A-Pad4)") (class "Default")
      (node (ref "3A") (pin "4") (pinfunction "4_4") (pintype "passive"))
    )
    (net (code "187") (name "unconnected-(3B-Pad5)") (class "Default")
      (node (ref "3B") (pin "5") (pinfunction "5_5") (pintype "passive"))
    )
    (net (code "188") (name "unconnected-(3B-Pad6)") (class "Default")
      (node (ref "3B") (pin "6") (pinfunction "6_6") (pintype "passive"))
    )
    (net (code "189") (name "unconnected-(3B-Pad7)") (class "Default")
      (node (ref "3B") (pin "7") (pinfunction "7_7") (pintype "passive"))
    )
    (net (code "190") (name "unconnected-(3B-Pad8)") (class "Default")
      (node (ref "3B") (pin "8") (pinfunction "8_8") (pintype "passive"))
    )
    (net (code "191") (name "unconnected-(3C-Pad4)") (class "Default")
      (node (ref "3C") (pin "4") (pinfunction "4_4") (pintype "passive"))
    )
    (net (code "192") (name "unconnected-(3C-Pad5)") (class "Default")
      (node (ref "3C") (pin "5") (pinfunction "5_5") (pintype "passive"))
    )
    (net (code "193") (name "unconnected-(3C-Pad6)") (class "Default")
      (node (ref "3C") (pin "6") (pinfunction "6_6") (pintype "passive"))
    )
    (net (code "194") (name "unconnected-(3C-Pad7)") (class "Default")
      (node (ref "3C") (pin "7") (pinfunction "7_7") (pintype "passive"))
    )
    (net (code "195") (name "unconnected-(4A-Pad7)") (class "Default")
      (node (ref "4A") (pin "7") (pinfunction "7_7") (pintype "passive"))
    )
    (net (code "196") (name "unconnected-(4A-Pad8)") (class "Default")
      (node (ref "4A") (pin "8") (pinfunction "8_8") (pintype "passive"))
    )
    (net (code "197") (name "unconnected-(5A-Pad3)") (class "Default")
      (node (ref "5A") (pin "3") (pinfunction "3_3") (pintype "passive"))
    )
    (net (code "198") (name "unconnected-(5A-Pad4)") (class "Default")
      (node (ref "5A") (pin "4") (pinfunction "4_4") (pintype "passive"))
    )
    (net (code "199") (name "unconnected-(5A-Pad5)") (class "Default")
      (node (ref "5A") (pin "5") (pinfunction "5_5") (pintype "passive"))
    )
    (net (code "200") (name "unconnected-(5A-Pad6)") (class "Default")
      (node (ref "5A") (pin "6") (pinfunction "6_6") (pintype "passive"))
    )
    (net (code "201") (name "unconnected-(5A-Pad7)") (class "Default")
      (node (ref "5A") (pin "7") (pinfunction "7_7") (pintype "passive"))
    )
    (net (code "202") (name "unconnected-(5A-Pad8)") (class "Default")
      (node (ref "5A") (pin "8") (pinfunction "8_8") (pintype "passive"))
    )
    (net (code "203") (name "unconnected-(5B-Pad3)") (class "Default")
      (node (ref "5B") (pin "3") (pinfunction "3_3") (pintype "passive"))
    )
    (net (code "204") (name "unconnected-(5B-Pad4)") (class "Default")
      (node (ref "5B") (pin "4") (pinfunction "4_4") (pintype "passive"))
    )
    (net (code "205") (name "unconnected-(5B-Pad5)") (class "Default")
      (node (ref "5B") (pin "5") (pinfunction "5_5") (pintype "passive"))
    )
    (net (code "206") (name "unconnected-(5B-Pad6)") (class "Default")
      (node (ref "5B") (pin "6") (pinfunction "6_6") (pintype "passive"))
    )
    (net (code "207") (name "unconnected-(5B-Pad7)") (class "Default")
      (node (ref "5B") (pin "7") (pinfunction "7_7") (pintype "passive"))
    )
    (net (code "208") (name "unconnected-(5B-Pad8)") (class "Default")
      (node (ref "5B") (pin "8") (pinfunction "8_8") (pintype "passive"))
    )
    (net (code "209") (name "unconnected-(5C-Pad1)") (class "Default")
      (node (ref "5C") (pin "1") (pinfunction "1_1") (pintype "passive"))
    )
    (net (code "210") (name "unconnected-(5C-Pad2)") (class "Default")
      (node (ref "5C") (pin "2") (pinfunction "2_2") (pintype "passive"))
    )
    (net (code "211") (name "unconnected-(5C-Pad3)") (class "Default")
      (node (ref "5C") (pin "3") (pinfunction "3_3") (pintype "passive"))
    )
    (net (code "212") (name "unconnected-(5D-Pad7)") (class "Default")
      (node (ref "5D") (pin "7") (pinfunction "7_7") (pintype "passive"))
    )
    (net (code "213") (name "unconnected-(6A-Pad1)") (class "Default")
      (node (ref "6A") (pin "1") (pinfunction "1_1") (pintype "passive"))
    )
    (net (code "214") (name "unconnected-(6A-Pad2)") (class "Default")
      (node (ref "6A") (pin "2") (pinfunction "2_2") (pintype "passive"))
    )
    (net (code "215") (name "unconnected-(6A-Pad3)") (class "Default")
      (node (ref "6A") (pin "3") (pinfunction "3_3") (pintype "passive"))
    )
    (net (code "216") (name "unconnected-(6A-Pad4)") (class "Default")
      (node (ref "6A") (pin "4") (pinfunction "4_4") (pintype "passive"))
    )
    (net (code "217") (name "unconnected-(6B-Pad7)") (class "Default")
      (node (ref "6B") (pin "7") (pinfunction "7_7") (pintype "passive"))
    )
    (net (code "218") (name "unconnected-(7A-Pad5)") (class "Default")
      (node (ref "7A") (pin "5") (pinfunction "5_5") (pintype "passive"))
    )
    (net (code "219") (name "unconnected-(7A-Pad6)") (class "Default")
      (node (ref "7A") (pin "6") (pinfunction "6_6") (pintype "passive"))
    )
    (net (code "220") (name "unconnected-(7A-Pad7)") (class "Default")
      (node (ref "7A") (pin "7") (pinfunction "7_7") (pintype "passive"))
    )
    (net (code "221") (name "unconnected-(7A-Pad8)") (class "Default")
      (node (ref "7A") (pin "8") (pinfunction "8_8") (pintype "passive"))
    )
    (net (code "222") (name "unconnected-(7D-Pad1)") (class "Default")
      (node (ref "7D") (pin "1") (pinfunction "1_1") (pintype "passive"))
    )
    (net (code "223") (name "unconnected-(7D-Pad2)") (class "Default")
      (node (ref "7D") (pin "2") (pinfunction "2_2") (pintype "passive"))
    )
    (net (code "224") (name "unconnected-(7D-Pad3)") (class "Default")
      (node (ref "7D") (pin "3") (pinfunction "3_3") (pintype "passive"))
    )
    (net (code "225") (name "unconnected-(7D-Pad4)") (class "Default")
      (node (ref "7D") (pin "4") (pinfunction "4_4") (pintype "passive"))
    )
    (net (code "226") (name "unconnected-(8A-Pad7)") (class "Default")
      (node (ref "8A") (pin "7") (pinfunction "7_7") (pintype "passive"))
    )
    (net (code "227") (name "unconnected-(8A-Pad8)") (class "Default")
      (node (ref "8A") (pin "8") (pinfunction "8_8") (pintype "passive"))
    )
    (net (code "228") (name "unconnected-(8B-Pad7)") (class "Default")
      (node (ref "8B") (pin "7") (pinfunction "7_7") (pintype "passive"))
    )
    (net (code "229") (name "unconnected-(8B-Pad8)") (class "Default")
      (node (ref "8B") (pin "8") (pinfunction "8_8") (pintype "passive"))
    )
    (net (code "230") (name "unconnected-(8C-Pad7)") (class "Default")
      (node (ref "8C") (pin "7") (pinfunction "7_7") (pintype "passive"))
    )
    (net (code "231") (name "unconnected-(9B-Pad7)") (class "Default")
      (node (ref "9B") (pin "7") (pinfunction "7_7") (pintype "passive"))
    )
    (net (code "232") (name "unconnected-(9B-Pad8)") (class "Default")
      (node (ref "9B") (pin "8") (pinfunction "8_8") (pintype "passive"))
    )
  )
)
